# ECUTeen3_5_rev_A_20180308_1928.net
KiCad netlist of a schematic drawn in EAGLE
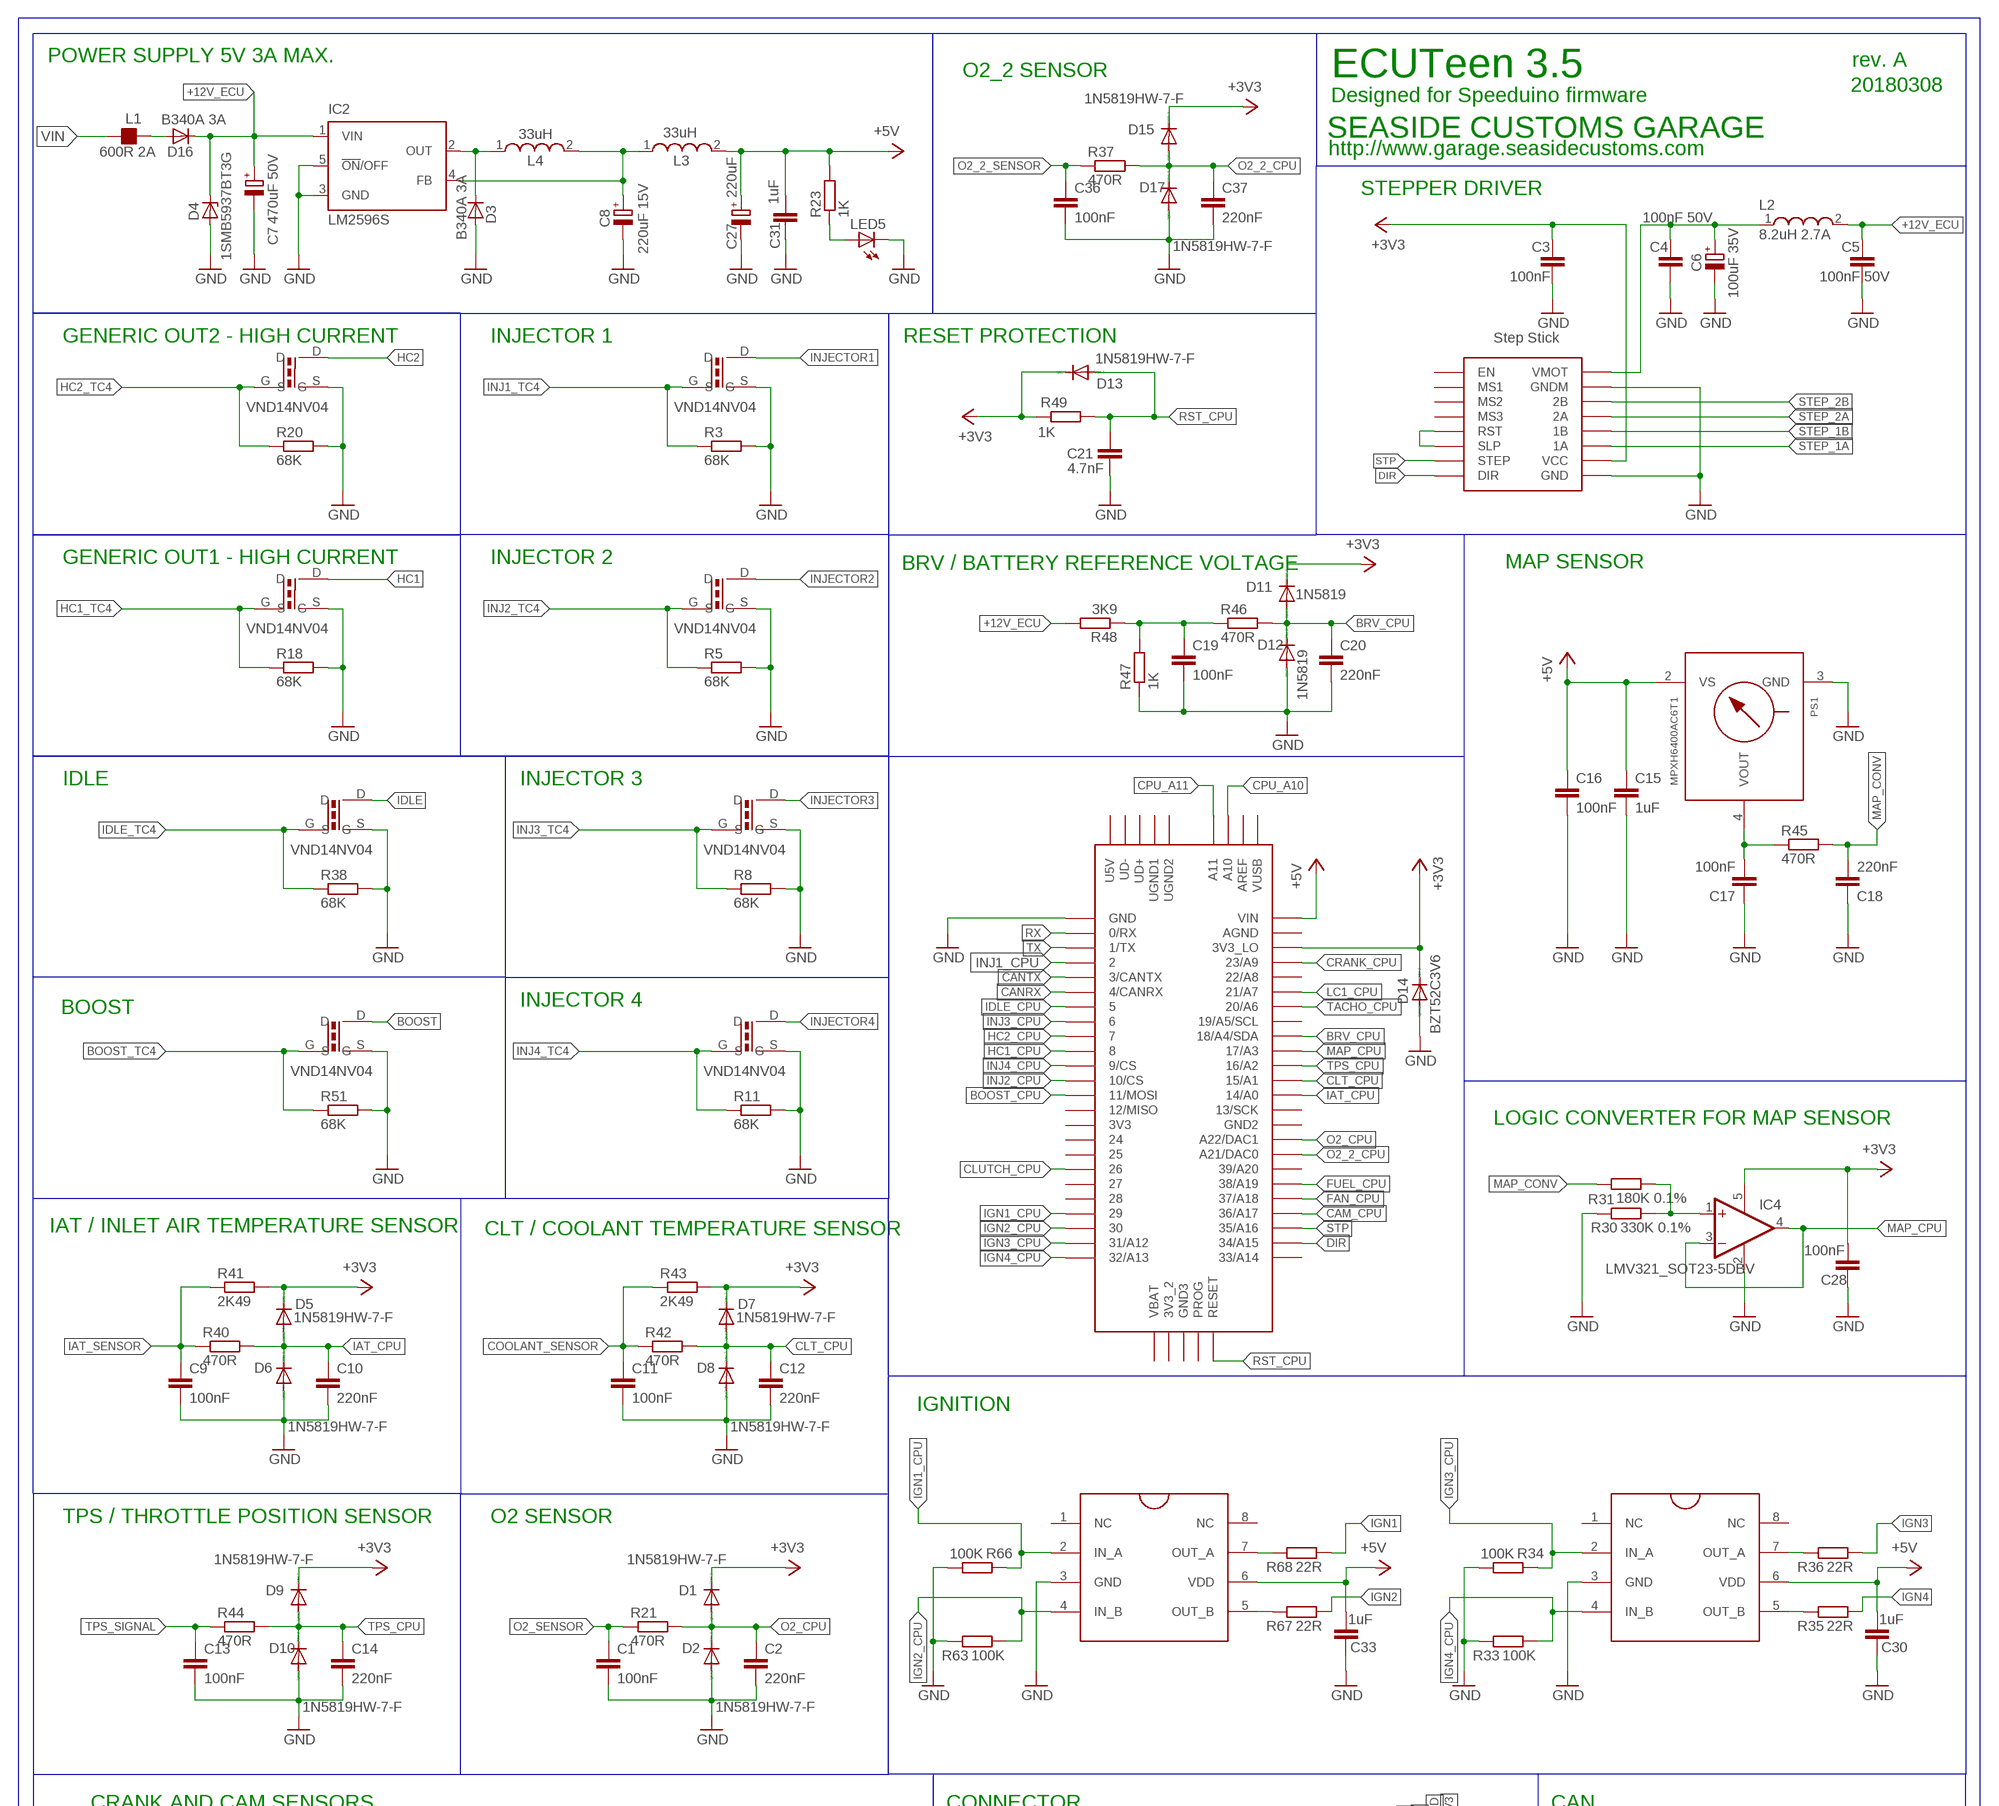
[diagram p0: schematic, sheet 1, part 1 of 2]
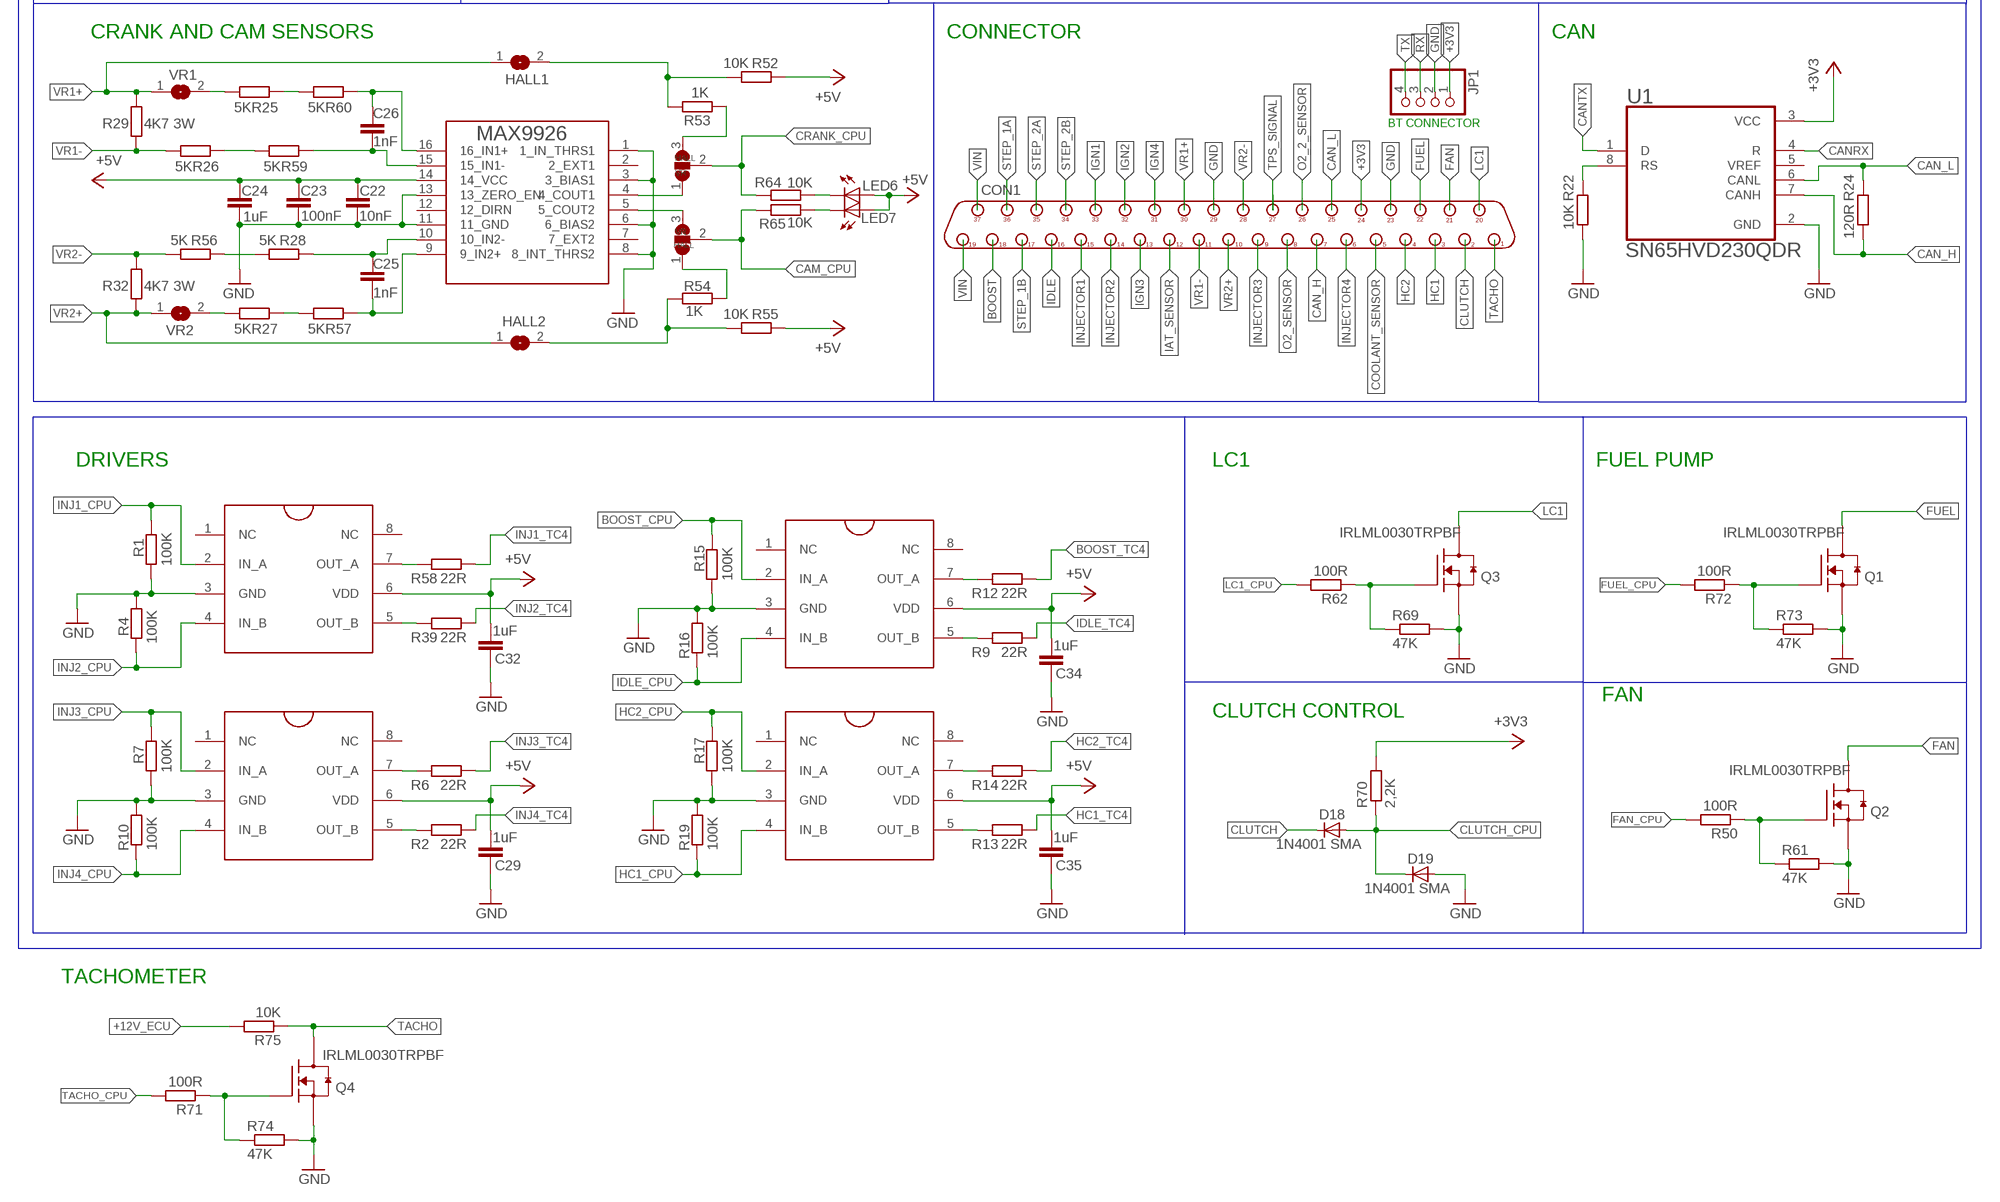
[diagram p1: schematic, sheet 1, part 2 of 2]

(export (version "E")
  (design (tool "Eeschema 10.0.6"))
  (components
    (comp (ref "C1")
      (value "100nF")
      (footprint "eagle-import:C0805")
      (libsource (lib "eagle-import") (part "C-EUC0805"))
    )
    (comp (ref "C2")
      (value "220nF")
      (footprint "eagle-import:C0805")
      (libsource (lib "eagle-import") (part "C-EUC0805"))
    )
    (comp (ref "C3")
      (value "100nF")
      (footprint "eagle-import:C0805")
      (libsource (lib "eagle-import") (part "C-EUC0805"))
    )
    (comp (ref "C4")
      (value "100nF 50V")
      (footprint "eagle-import:C0805")
      (libsource (lib "eagle-import") (part "C-EUC0805"))
    )
    (comp (ref "C5")
      (value "100nF 50V")
      (footprint "eagle-import:C0805")
      (libsource (lib "eagle-import") (part "C-EUC0805"))
    )
    (comp (ref "C6")
      (value "100uF 35V")
      (footprint "eagle-import:PANASONIC_D")
      (libsource (lib "eagle-import") (part "CPOL-EUD"))
    )
    (comp (ref "C7")
      (value "470uF 50V")
      (footprint "eagle-import:PANASONIC_D")
      (libsource (lib "eagle-import") (part "CPOL-EUD"))
    )
    (comp (ref "C8")
      (value "220uF 15V")
      (footprint "eagle-import:PANASONIC_D")
      (libsource (lib "eagle-import") (part "CPOL-EUD"))
    )
    (comp (ref "C9")
      (value "100nF")
      (footprint "eagle-import:C0805")
      (libsource (lib "eagle-import") (part "C-EUC0805"))
    )
    (comp (ref "C10")
      (value "220nF")
      (footprint "eagle-import:C0805")
      (libsource (lib "eagle-import") (part "C-EUC0805"))
    )
    (comp (ref "C11")
      (value "100nF")
      (footprint "eagle-import:C0805")
      (libsource (lib "eagle-import") (part "C-EUC0805"))
    )
    (comp (ref "C12")
      (value "220nF")
      (footprint "eagle-import:C0805")
      (libsource (lib "eagle-import") (part "C-EUC0805"))
    )
    (comp (ref "C13")
      (value "100nF")
      (footprint "eagle-import:C0805")
      (libsource (lib "eagle-import") (part "C-EUC0805"))
    )
    (comp (ref "C14")
      (value "220nF")
      (footprint "eagle-import:C0805")
      (libsource (lib "eagle-import") (part "C-EUC0805"))
    )
    (comp (ref "C15")
      (value "1uF")
      (footprint "eagle-import:C0805")
      (libsource (lib "eagle-import") (part "C-EUC0805"))
    )
    (comp (ref "C16")
      (value "100nF")
      (footprint "eagle-import:C0805")
      (libsource (lib "eagle-import") (part "C-EUC0805"))
    )
    (comp (ref "C17")
      (value "100nF")
      (footprint "eagle-import:C0805")
      (libsource (lib "eagle-import") (part "C-EUC0805"))
    )
    (comp (ref "C18")
      (value "220nF")
      (footprint "eagle-import:C0805")
      (libsource (lib "eagle-import") (part "C-EUC0805"))
    )
    (comp (ref "C19")
      (value "100nF")
      (footprint "eagle-import:C0805")
      (libsource (lib "eagle-import") (part "C-EUC0805"))
    )
    (comp (ref "C20")
      (value "220nF")
      (footprint "eagle-import:C0805")
      (libsource (lib "eagle-import") (part "C-EUC0805"))
    )
    (comp (ref "C21")
      (value "4.7nF")
      (footprint "eagle-import:C0805")
      (libsource (lib "eagle-import") (part "C-EUC0805"))
    )
    (comp (ref "C22")
      (value "10nF")
      (footprint "eagle-import:C0805")
      (libsource (lib "eagle-import") (part "C-EUC0805"))
    )
    (comp (ref "C23")
      (value "100nF")
      (footprint "eagle-import:C0805")
      (libsource (lib "eagle-import") (part "C-EUC0805"))
    )
    (comp (ref "C24")
      (value "1uF")
      (footprint "eagle-import:C0805")
      (libsource (lib "eagle-import") (part "C-EUC0805"))
    )
    (comp (ref "C25")
      (value "1nF")
      (footprint "eagle-import:C0805")
      (libsource (lib "eagle-import") (part "C-EUC0805"))
    )
    (comp (ref "C26")
      (value "1nF")
      (footprint "eagle-import:C0805")
      (libsource (lib "eagle-import") (part "C-EUC0805"))
    )
    (comp (ref "C27")
      (value "220uF")
      (footprint "eagle-import:PANASONIC_D")
      (libsource (lib "eagle-import") (part "CPOL-EUD"))
    )
    (comp (ref "C28")
      (value "100nF")
      (footprint "eagle-import:C0805")
      (libsource (lib "eagle-import") (part "C-EUC0805"))
    )
    (comp (ref "C29")
      (value "1uF")
      (footprint "eagle-import:C0805")
      (libsource (lib "eagle-import") (part "C-EUC0805"))
    )
    (comp (ref "C30")
      (value "1uF")
      (footprint "eagle-import:C0805")
      (libsource (lib "eagle-import") (part "C-EUC0805"))
    )
    (comp (ref "C31")
      (value "1uF")
      (footprint "eagle-import:C0805")
      (libsource (lib "eagle-import") (part "C-EUC0805"))
    )
    (comp (ref "C32")
      (value "1uF")
      (footprint "eagle-import:C0805")
      (libsource (lib "eagle-import") (part "C-EUC0805"))
    )
    (comp (ref "C33")
      (value "1uF")
      (footprint "eagle-import:C0805")
      (libsource (lib "eagle-import") (part "C-EUC0805"))
    )
    (comp (ref "C34")
      (value "1uF")
      (footprint "eagle-import:C0805")
      (libsource (lib "eagle-import") (part "C-EUC0805"))
    )
    (comp (ref "C35")
      (value "1uF")
      (footprint "eagle-import:C0805")
      (libsource (lib "eagle-import") (part "C-EUC0805"))
    )
    (comp (ref "C36")
      (value "100nF")
      (footprint "eagle-import:C0805")
      (libsource (lib "eagle-import") (part "C-EUC0805"))
    )
    (comp (ref "C37")
      (value "220nF")
      (footprint "eagle-import:C0805")
      (libsource (lib "eagle-import") (part "C-EUC0805"))
    )
    (comp (ref "CON1")
      (value "DB37M/90")
      (footprint "eagle-import:D-37M_90")
      (libsource (lib "eagle-import") (part "DB37M/90"))
    )
    (comp (ref "D1")
      (value "1N5819HW-7-F")
      (footprint "eagle-import:SOD123")
      (libsource (lib "eagle-import") (part "diode_DIODE-SOD123"))
    )
    (comp (ref "D2")
      (value "1N5819HW-7-F")
      (footprint "eagle-import:SOD123")
      (libsource (lib "eagle-import") (part "diode_DIODE-SOD123"))
    )
    (comp (ref "D3")
      (value "B340A 3A")
      (footprint "eagle-import:DO214AC")
      (fields (field (name "MF") "Fairchild") (field (name "MPN") "S1A"))
      (libsource (lib "eagle-import") (part "S1A"))
    )
    (comp (ref "D4")
      (value "1SMB5937BT3G")
      (footprint "eagle-import:SMB")
      (libsource (lib "eagle-import") (part "ZENER-DIODESMB"))
    )
    (comp (ref "D5")
      (value "1N5819HW-7-F")
      (footprint "eagle-import:SOD123")
      (libsource (lib "eagle-import") (part "diode_DIODE-SOD123"))
    )
    (comp (ref "D6")
      (value "1N5819HW-7-F")
      (footprint "eagle-import:SOD123")
      (libsource (lib "eagle-import") (part "diode_DIODE-SOD123"))
    )
    (comp (ref "D7")
      (value "1N5819HW-7-F")
      (footprint "eagle-import:SOD123")
      (libsource (lib "eagle-import") (part "diode_DIODE-SOD123"))
    )
    (comp (ref "D8")
      (value "1N5819HW-7-F")
      (footprint "eagle-import:SOD123")
      (libsource (lib "eagle-import") (part "diode_DIODE-SOD123"))
    )
    (comp (ref "D9")
      (value "1N5819HW-7-F")
      (footprint "eagle-import:SOD123")
      (libsource (lib "eagle-import") (part "diode_DIODE-SOD123"))
    )
    (comp (ref "D10")
      (value "1N5819HW-7-F")
      (footprint "eagle-import:SOD123")
      (libsource (lib "eagle-import") (part "diode_DIODE-SOD123"))
    )
    (comp (ref "D11")
      (value "1N5819")
      (footprint "eagle-import:SOD123")
      (libsource (lib "eagle-import") (part "diode_DIODE-SOD123"))
    )
    (comp (ref "D12")
      (value "1N5819")
      (footprint "eagle-import:SOD123")
      (libsource (lib "eagle-import") (part "diode_DIODE-SOD123"))
    )
    (comp (ref "D13")
      (value "1N5819HW-7-F")
      (footprint "eagle-import:SOD123")
      (libsource (lib "eagle-import") (part "diode_DIODE-SOD123"))
    )
    (comp (ref "D14")
      (value "BZT52C3V6")
      (footprint "eagle-import:SOD123")
      (libsource (lib "eagle-import") (part "DIODE-SOD123"))
    )
    (comp (ref "D15")
      (value "1N5819HW-7-F")
      (footprint "eagle-import:SOD123")
      (libsource (lib "eagle-import") (part "diode_DIODE-SOD123"))
    )
    (comp (ref "D16")
      (value "B340A 3A")
      (footprint "eagle-import:DO214AC")
      (fields (field (name "MF") "Fairchild") (field (name "MPN") "S1A"))
      (libsource (lib "eagle-import") (part "S1A"))
    )
    (comp (ref "D17")
      (value "1N5819HW-7-F")
      (footprint "eagle-import:SOD123")
      (libsource (lib "eagle-import") (part "diode_DIODE-SOD123"))
    )
    (comp (ref "D18")
      (value "1N4001 SMA")
      (footprint "eagle-import:DO214AC")
      (fields (field (name "MF") "Fairchild") (field (name "MPN") "S1A"))
      (libsource (lib "eagle-import") (part "S1A"))
    )
    (comp (ref "D19")
      (value "1N4001 SMA")
      (footprint "eagle-import:DO214AC")
      (fields (field (name "MF") "Fairchild") (field (name "MPN") "S1A"))
      (libsource (lib "eagle-import") (part "S1A"))
    )
    (comp (ref "IC2")
      (value "LM2596S")
      (footprint "eagle-import:TO263-5")
      (fields (field (name "MF") "NATIONAL SEMICONDUCTOR") (field (name "MPN") "LM2596S-ADJ/NOPB"))
      (libsource (lib "eagle-import") (part "LM2596S"))
    )
    (comp (ref "IC4")
      (value "LMV321_SOT23-5DBV")
      (footprint "eagle-import:SOT23-5")
      (libsource (lib "eagle-import") (part "LMV321_SOT23-5DBV"))
    )
    (comp (ref "JMP1")
      (value "SJ2W")
      (footprint "eagle-import:SJ_2")
      (libsource (lib "eagle-import") (part "SJ2W"))
    )
    (comp (ref "JMP2")
      (value "SJ2W")
      (footprint "eagle-import:SJ_2")
      (libsource (lib "eagle-import") (part "SJ2W"))
    )
    (comp (ref "JP1")
      (value "PINHD-1X4")
      (footprint "eagle-import:1X04")
      (libsource (lib "eagle-import") (part "PINHD-1X4"))
    )
    (comp (ref "L1")
      (value "600R 2A")
      (footprint "eagle-import:L1206")
      (libsource (lib "eagle-import") (part "FB_1206"))
    )
    (comp (ref "L2")
      (value "8.2uH 2.7A")
      (footprint "eagle-import:WE-PD_7332_7345_PLASTIC_BASE")
      (libsource (lib "eagle-import") (part "WE-PD_7332/7345_PLASTIC_BASE"))
    )
    (comp (ref "L3")
      (value "33uH")
      (footprint "eagle-import:WE-LHMI_7030_7050")
      (libsource (lib "eagle-import") (part "WE-LHMI_7030/7050"))
    )
    (comp (ref "L4")
      (value "33uH")
      (footprint "eagle-import:WE-LHMI_7030_7050")
      (libsource (lib "eagle-import") (part "WE-LHMI_7030/7050"))
    )
    (comp (ref "LED5")
      (value "LEDCHIP-LED0805")
      (footprint "eagle-import:CHIP-LED0805")
      (libsource (lib "eagle-import") (part "LEDCHIP-LED0805"))
    )
    (comp (ref "LED6")
      (value "LEDCHIP-LED0805")
      (footprint "eagle-import:CHIP-LED0805")
      (libsource (lib "eagle-import") (part "LEDCHIP-LED0805"))
    )
    (comp (ref "LED7")
      (value "LEDCHIP-LED0805")
      (footprint "eagle-import:CHIP-LED0805")
      (libsource (lib "eagle-import") (part "LEDCHIP-LED0805"))
    )
    (comp (ref "PS1")
      (value "MPXH6400AC6T1")
      (footprint "eagle-import:1317A")
      (libsource (lib "eagle-import") (part "MPXH6400AC6T1"))
    )
    (comp (ref "Q1")
      (value "IRLML0030TRPBF")
      (footprint "eagle-import:SOT95P280X135-3N")
      (libsource (lib "eagle-import") (part "MOSFET-NCH_SOT-23"))
    )
    (comp (ref "Q2")
      (value "IRLML0030TRPBF")
      (footprint "eagle-import:SOT95P280X135-3N")
      (libsource (lib "eagle-import") (part "MOSFET-NCH_SOT-23"))
    )
    (comp (ref "Q3")
      (value "IRLML0030TRPBF")
      (footprint "eagle-import:SOT95P280X135-3N")
      (libsource (lib "eagle-import") (part "MOSFET-NCH_SOT-23"))
    )
    (comp (ref "Q4")
      (value "IRLML0030TRPBF")
      (footprint "eagle-import:SOT95P280X135-3N")
      (libsource (lib "eagle-import") (part "MOSFET-NCH_SOT-23"))
    )
    (comp (ref "R1")
      (value "100K")
      (footprint "eagle-import:R0805")
      (libsource (lib "eagle-import") (part "R-EU_R0805"))
    )
    (comp (ref "R2")
      (value "22R")
      (footprint "eagle-import:R0805")
      (libsource (lib "eagle-import") (part "R-EU_R0805"))
    )
    (comp (ref "R3")
      (value "68K")
      (footprint "eagle-import:R0805")
      (libsource (lib "eagle-import") (part "R-EU_R0805"))
    )
    (comp (ref "R4")
      (value "100K")
      (footprint "eagle-import:R0805")
      (libsource (lib "eagle-import") (part "R-EU_R0805"))
    )
    (comp (ref "R5")
      (value "68K")
      (footprint "eagle-import:R0805")
      (libsource (lib "eagle-import") (part "R-EU_R0805"))
    )
    (comp (ref "R6")
      (value "22R")
      (footprint "eagle-import:R0805")
      (libsource (lib "eagle-import") (part "R-EU_R0805"))
    )
    (comp (ref "R7")
      (value "100K")
      (footprint "eagle-import:R0805")
      (libsource (lib "eagle-import") (part "R-EU_R0805"))
    )
    (comp (ref "R8")
      (value "68K")
      (footprint "eagle-import:R0805")
      (libsource (lib "eagle-import") (part "R-EU_R0805"))
    )
    (comp (ref "R9")
      (value "22R")
      (footprint "eagle-import:R0805")
      (libsource (lib "eagle-import") (part "R-EU_R0805"))
    )
    (comp (ref "R10")
      (value "100K")
      (footprint "eagle-import:R0805")
      (libsource (lib "eagle-import") (part "R-EU_R0805"))
    )
    (comp (ref "R11")
      (value "68K")
      (footprint "eagle-import:R0805")
      (libsource (lib "eagle-import") (part "R-EU_R0805"))
    )
    (comp (ref "R12")
      (value "22R")
      (footprint "eagle-import:R0805")
      (libsource (lib "eagle-import") (part "R-EU_R0805"))
    )
    (comp (ref "R13")
      (value "22R")
      (footprint "eagle-import:R0805")
      (libsource (lib "eagle-import") (part "R-EU_R0805"))
    )
    (comp (ref "R14")
      (value "22R")
      (footprint "eagle-import:R0805")
      (libsource (lib "eagle-import") (part "R-EU_R0805"))
    )
    (comp (ref "R15")
      (value "100K")
      (footprint "eagle-import:R0805")
      (libsource (lib "eagle-import") (part "R-EU_R0805"))
    )
    (comp (ref "R16")
      (value "100K")
      (footprint "eagle-import:R0805")
      (libsource (lib "eagle-import") (part "R-EU_R0805"))
    )
    (comp (ref "R17")
      (value "100K")
      (footprint "eagle-import:R0805")
      (libsource (lib "eagle-import") (part "R-EU_R0805"))
    )
    (comp (ref "R18")
      (value "68K")
      (footprint "eagle-import:R0805")
      (libsource (lib "eagle-import") (part "R-EU_R0805"))
    )
    (comp (ref "R19")
      (value "100K")
      (footprint "eagle-import:R0805")
      (libsource (lib "eagle-import") (part "R-EU_R0805"))
    )
    (comp (ref "R20")
      (value "68K")
      (footprint "eagle-import:R0805")
      (libsource (lib "eagle-import") (part "R-EU_R0805"))
    )
    (comp (ref "R21")
      (value "470R")
      (footprint "eagle-import:R0805")
      (libsource (lib "eagle-import") (part "R-EU_R0805"))
    )
    (comp (ref "R22")
      (value "10K")
      (footprint "eagle-import:R0805")
      (libsource (lib "eagle-import") (part "R-EU_R0805"))
    )
    (comp (ref "R23")
      (value "1K")
      (footprint "eagle-import:R0805")
      (libsource (lib "eagle-import") (part "R-EU_R0805"))
    )
    (comp (ref "R24")
      (value "120R")
      (footprint "eagle-import:R0805")
      (libsource (lib "eagle-import") (part "R-EU_R0805"))
    )
    (comp (ref "R25")
      (value "5K")
      (footprint "eagle-import:R0805")
      (libsource (lib "eagle-import") (part "R-EU_R0805"))
    )
    (comp (ref "R26")
      (value "5K")
      (footprint "eagle-import:R0805")
      (libsource (lib "eagle-import") (part "R-EU_R0805"))
    )
    (comp (ref "R27")
      (value "5K")
      (footprint "eagle-import:R0805")
      (libsource (lib "eagle-import") (part "R-EU_R0805"))
    )
    (comp (ref "R28")
      (value "5K")
      (footprint "eagle-import:R0805")
      (libsource (lib "eagle-import") (part "R-EU_R0805"))
    )
    (comp (ref "R29")
      (value "4K7 3W")
      (footprint "eagle-import:R2512")
      (libsource (lib "eagle-import") (part "R-EU_R2512"))
    )
    (comp (ref "R30")
      (value "330K 0.1%")
      (footprint "eagle-import:R0805")
      (libsource (lib "eagle-import") (part "R-EU_R0805"))
    )
    (comp (ref "R31")
      (value "180K 0.1%")
      (footprint "eagle-import:R0805")
      (libsource (lib "eagle-import") (part "R-EU_R0805"))
    )
    (comp (ref "R32")
      (value "4K7 3W")
      (footprint "eagle-import:R2512")
      (libsource (lib "eagle-import") (part "R-EU_R2512"))
    )
    (comp (ref "R33")
      (value "100K")
      (footprint "eagle-import:R0805")
      (libsource (lib "eagle-import") (part "R-EU_R0805"))
    )
    (comp (ref "R34")
      (value "100K")
      (footprint "eagle-import:R0805")
      (libsource (lib "eagle-import") (part "R-EU_R0805"))
    )
    (comp (ref "R35")
      (value "22R")
      (footprint "eagle-import:M1206")
      (libsource (lib "eagle-import") (part "R-EU_M1206"))
    )
    (comp (ref "R36")
      (value "22R")
      (footprint "eagle-import:M1206")
      (libsource (lib "eagle-import") (part "R-EU_M1206"))
    )
    (comp (ref "R37")
      (value "470R")
      (footprint "eagle-import:R0805")
      (libsource (lib "eagle-import") (part "R-EU_R0805"))
    )
    (comp (ref "R38")
      (value "68K")
      (footprint "eagle-import:R0805")
      (libsource (lib "eagle-import") (part "R-EU_R0805"))
    )
    (comp (ref "R39")
      (value "22R")
      (footprint "eagle-import:R0805")
      (libsource (lib "eagle-import") (part "R-EU_R0805"))
    )
    (comp (ref "R40")
      (value "470R")
      (footprint "eagle-import:R0805")
      (libsource (lib "eagle-import") (part "R-EU_R0805"))
    )
    (comp (ref "R41")
      (value "2K49")
      (footprint "eagle-import:R0805")
      (libsource (lib "eagle-import") (part "R-EU_R0805"))
    )
    (comp (ref "R42")
      (value "470R")
      (footprint "eagle-import:R0805")
      (libsource (lib "eagle-import") (part "R-EU_R0805"))
    )
    (comp (ref "R43")
      (value "2K49")
      (footprint "eagle-import:R0805")
      (libsource (lib "eagle-import") (part "R-EU_R0805"))
    )
    (comp (ref "R44")
      (value "470R")
      (footprint "eagle-import:R0805")
      (libsource (lib "eagle-import") (part "R-EU_R0805"))
    )
    (comp (ref "R45")
      (value "470R")
      (footprint "eagle-import:R0805")
      (libsource (lib "eagle-import") (part "R-EU_R0805"))
    )
    (comp (ref "R46")
      (value "470R")
      (footprint "eagle-import:R0805")
      (libsource (lib "eagle-import") (part "R-EU_R0805"))
    )
    (comp (ref "R47")
      (value "1K")
      (footprint "eagle-import:R0805")
      (libsource (lib "eagle-import") (part "R-EU_R0805"))
    )
    (comp (ref "R48")
      (value "3K9")
      (footprint "eagle-import:R0805")
      (libsource (lib "eagle-import") (part "R-EU_R0805"))
    )
    (comp (ref "R49")
      (value "1K")
      (footprint "eagle-import:R0805")
      (libsource (lib "eagle-import") (part "R-EU_R0805"))
    )
    (comp (ref "R50")
      (value "100R")
      (footprint "eagle-import:R0805")
      (libsource (lib "eagle-import") (part "R-EU_R0805"))
    )
    (comp (ref "R51")
      (value "68K")
      (footprint "eagle-import:R0805")
      (libsource (lib "eagle-import") (part "R-EU_R0805"))
    )
    (comp (ref "R52")
      (value "10K")
      (footprint "eagle-import:R0805")
      (libsource (lib "eagle-import") (part "R-EU_R0805"))
    )
    (comp (ref "R53")
      (value "1K")
      (footprint "eagle-import:R0805")
      (libsource (lib "eagle-import") (part "R-EU_R0805"))
    )
    (comp (ref "R54")
      (value "1K")
      (footprint "eagle-import:R0805")
      (libsource (lib "eagle-import") (part "R-EU_R0805"))
    )
    (comp (ref "R55")
      (value "10K")
      (footprint "eagle-import:R0805")
      (libsource (lib "eagle-import") (part "R-EU_R0805"))
    )
    (comp (ref "R56")
      (value "5K")
      (footprint "eagle-import:R0805")
      (libsource (lib "eagle-import") (part "R-EU_R0805"))
    )
    (comp (ref "R57")
      (value "5K")
      (footprint "eagle-import:R0805")
      (libsource (lib "eagle-import") (part "R-EU_R0805"))
    )
    (comp (ref "R58")
      (value "22R")
      (footprint "eagle-import:R0805")
      (libsource (lib "eagle-import") (part "R-EU_R0805"))
    )
    (comp (ref "R59")
      (value "5K")
      (footprint "eagle-import:R0805")
      (libsource (lib "eagle-import") (part "R-EU_R0805"))
    )
    (comp (ref "R60")
      (value "5K")
      (footprint "eagle-import:R0805")
      (libsource (lib "eagle-import") (part "R-EU_R0805"))
    )
    (comp (ref "R61")
      (value "47K")
      (footprint "eagle-import:R0805")
      (libsource (lib "eagle-import") (part "R-EU_R0805"))
    )
    (comp (ref "R62")
      (value "100R")
      (footprint "eagle-import:R0805")
      (libsource (lib "eagle-import") (part "R-EU_R0805"))
    )
    (comp (ref "R63")
      (value "100K")
      (footprint "eagle-import:R0805")
      (libsource (lib "eagle-import") (part "R-EU_R0805"))
    )
    (comp (ref "R64")
      (value "10K")
      (footprint "eagle-import:R0805")
      (libsource (lib "eagle-import") (part "R-EU_R0805"))
    )
    (comp (ref "R65")
      (value "10K")
      (footprint "eagle-import:R0805")
      (libsource (lib "eagle-import") (part "R-EU_R0805"))
    )
    (comp (ref "R66")
      (value "100K")
      (footprint "eagle-import:R0805")
      (libsource (lib "eagle-import") (part "R-EU_R0805"))
    )
    (comp (ref "R67")
      (value "22R")
      (footprint "eagle-import:M1206")
      (libsource (lib "eagle-import") (part "R-EU_M1206"))
    )
    (comp (ref "R68")
      (value "22R")
      (footprint "eagle-import:M1206")
      (libsource (lib "eagle-import") (part "R-EU_M1206"))
    )
    (comp (ref "R69")
      (value "47K")
      (footprint "eagle-import:R0805")
      (libsource (lib "eagle-import") (part "R-EU_R0805"))
    )
    (comp (ref "R70")
      (value "2,2K")
      (footprint "eagle-import:R0805")
      (libsource (lib "eagle-import") (part "R-EU_R0805"))
    )
    (comp (ref "R71")
      (value "100R")
      (footprint "eagle-import:R0805")
      (libsource (lib "eagle-import") (part "R-EU_R0805"))
    )
    (comp (ref "R72")
      (value "100R")
      (footprint "eagle-import:R0805")
      (libsource (lib "eagle-import") (part "R-EU_R0805"))
    )
    (comp (ref "R73")
      (value "47K")
      (footprint "eagle-import:R0805")
      (libsource (lib "eagle-import") (part "R-EU_R0805"))
    )
    (comp (ref "R74")
      (value "47K")
      (footprint "eagle-import:R0805")
      (libsource (lib "eagle-import") (part "R-EU_R0805"))
    )
    (comp (ref "R75")
      (value "10K")
      (footprint "eagle-import:R0805")
      (libsource (lib "eagle-import") (part "R-EU_R0805"))
    )
    (comp (ref "SJ3")
      (value "VR2")
      (footprint "eagle-import:SJ")
      (libsource (lib "eagle-import") (part "SJ"))
    )
    (comp (ref "SJ4")
      (value "VR1")
      (footprint "eagle-import:SJ")
      (libsource (lib "eagle-import") (part "SJ"))
    )
    (comp (ref "SJ5")
      (value "HALL2")
      (footprint "eagle-import:SJ")
      (libsource (lib "eagle-import") (part "SJ"))
    )
    (comp (ref "SJ6")
      (value "HALL1")
      (footprint "eagle-import:SJ")
      (libsource (lib "eagle-import") (part "SJ"))
    )
    (comp (ref "STEPSTICK-X")
      (value "STEP-STICK")
      (footprint "eagle-import:STEP-STICK")
      (libsource (lib "eagle-import") (part "STEP-STICK"))
    )
    (comp (ref "U$1")
      (value "TEENSY_3.5/3.6")
      (footprint "eagle-import:TEENSY_3.5_3.6")
      (libsource (lib "eagle-import") (part "TEENSY_3.5/3.6"))
    )
    (comp (ref "U$2")
      (value "DPAK_N-CHANNEL_MOSFET")
      (footprint "eagle-import:DPAK_N-CHANNEL_MOSFET")
      (libsource (lib "eagle-import") (part "DPAK_N-CHANNEL_MOSFET"))
    )
    (comp (ref "U$3")
      (value "DPAK_N-CHANNEL_MOSFET")
      (footprint "eagle-import:DPAK_N-CHANNEL_MOSFET")
      (libsource (lib "eagle-import") (part "DPAK_N-CHANNEL_MOSFET"))
    )
    (comp (ref "U$4")
      (value "DPAK_N-CHANNEL_MOSFET")
      (footprint "eagle-import:DPAK_N-CHANNEL_MOSFET")
      (libsource (lib "eagle-import") (part "DPAK_N-CHANNEL_MOSFET"))
    )
    (comp (ref "U$5")
      (value "DPAK_N-CHANNEL_MOSFET")
      (footprint "eagle-import:DPAK_N-CHANNEL_MOSFET")
      (libsource (lib "eagle-import") (part "DPAK_N-CHANNEL_MOSFET"))
    )
    (comp (ref "U$6")
      (value "DPAK_N-CHANNEL_MOSFET")
      (footprint "eagle-import:DPAK_N-CHANNEL_MOSFET")
      (libsource (lib "eagle-import") (part "DPAK_N-CHANNEL_MOSFET"))
    )
    (comp (ref "U$7")
      (value "TC427SO-8")
      (footprint "eagle-import:SO-8")
      (libsource (lib "eagle-import") (part "TC427SO-8"))
    )
    (comp (ref "U$8")
      (value "DPAK_N-CHANNEL_MOSFET")
      (footprint "eagle-import:DPAK_N-CHANNEL_MOSFET")
      (libsource (lib "eagle-import") (part "DPAK_N-CHANNEL_MOSFET"))
    )
    (comp (ref "U$9")
      (value "TC427SO-8")
      (footprint "eagle-import:SO-8")
      (libsource (lib "eagle-import") (part "TC427SO-8"))
    )
    (comp (ref "U$10")
      (value "MAX9926")
      (footprint "eagle-import:QSOP16")
      (libsource (lib "eagle-import") (part "MAX9926"))
    )
    (comp (ref "U$11")
      (value "TC427SO-8")
      (footprint "eagle-import:SO-8")
      (libsource (lib "eagle-import") (part "TC427SO-8"))
    )
    (comp (ref "U$12")
      (value "DPAK_N-CHANNEL_MOSFET")
      (footprint "eagle-import:DPAK_N-CHANNEL_MOSFET")
      (libsource (lib "eagle-import") (part "DPAK_N-CHANNEL_MOSFET"))
    )
    (comp (ref "U$13")
      (value "DPAK_N-CHANNEL_MOSFET")
      (footprint "eagle-import:DPAK_N-CHANNEL_MOSFET")
      (libsource (lib "eagle-import") (part "DPAK_N-CHANNEL_MOSFET"))
    )
    (comp (ref "U$14")
      (value "TC427SO-8")
      (footprint "eagle-import:SO-8")
      (libsource (lib "eagle-import") (part "TC427SO-8"))
    )
    (comp (ref "U$15")
      (value "TC427SO-8")
      (footprint "eagle-import:SO-8")
      (libsource (lib "eagle-import") (part "TC427SO-8"))
    )
    (comp (ref "U$16")
      (value "TC427SO-8")
      (footprint "eagle-import:SO-8")
      (libsource (lib "eagle-import") (part "TC427SO-8"))
    )
    (comp (ref "U1")
      (value "SN65HVD230QDR")
      (footprint "eagle-import:SOIC127P600X175-8N")
      (fields (field (name "MF") "Texas Instruments"))
      (libsource (lib "eagle-import") (part "SN65HVD230QDR"))
    )
  )
  (nets
    (net (code "2") (name "+3V3") (class "Default")
      (node (ref "C28") (pin "2") (pinfunction "2_2") (pintype "passive"))
      (node (ref "C3") (pin "1") (pinfunction "1_1") (pintype "passive"))
      (node (ref "CON1") (pin "24") (pinfunction "24_24") (pintype "passive"))
      (node (ref "D1") (pin "C") (pinfunction "C_C") (pintype "passive"))
      (node (ref "D11") (pin "C") (pinfunction "C_C") (pintype "passive"))
      (node (ref "D13") (pin "C") (pinfunction "C_C") (pintype "passive"))
      (node (ref "D14") (pin "C") (pinfunction "C_C") (pintype "passive"))
      (node (ref "D15") (pin "C") (pinfunction "C_C") (pintype "passive"))
      (node (ref "D5") (pin "C") (pinfunction "C_C") (pintype "passive"))
      (node (ref "D7") (pin "C") (pinfunction "C_C") (pintype "passive"))
      (node (ref "D9") (pin "C") (pinfunction "C_C") (pintype "passive"))
      (node (ref "IC4") (pin "5") (pinfunction "V+_5") (pintype "power_in"))
      (node (ref "JP1") (pin "1") (pinfunction "1_1") (pintype "passive"))
      (node (ref "R41") (pin "2") (pinfunction "2_2") (pintype "passive"))
      (node (ref "R43") (pin "2") (pinfunction "2_2") (pintype "passive"))
      (node (ref "R49") (pin "1") (pinfunction "1_1") (pintype "passive"))
      (node (ref "R70") (pin "2") (pinfunction "2_2") (pintype "passive"))
      (node (ref "STEPSTICK-X") (pin "VCC") (pinfunction "VCC_VCC") (pintype "bidirectional"))
      (node (ref "U$1") (pin "3V3_LO") (pinfunction "3V3_LO_3V3_LO") (pintype "bidirectional"))
      (node (ref "U1") (pin "3") (pinfunction "VCC_3") (pintype "power_in"))
    )
    (net (code "3") (name "+5V") (class "Default")
      (node (ref "C15") (pin "1") (pinfunction "1_1") (pintype "passive"))
      (node (ref "C16") (pin "1") (pinfunction "1_1") (pintype "passive"))
      (node (ref "C22") (pin "1") (pinfunction "1_1") (pintype "passive"))
      (node (ref "C23") (pin "1") (pinfunction "1_1") (pintype "passive"))
      (node (ref "C24") (pin "1") (pinfunction "1_1") (pintype "passive"))
      (node (ref "C27") (pin "+") (pinfunction "+_+") (pintype "passive"))
      (node (ref "C29") (pin "2") (pinfunction "2_2") (pintype "passive"))
      (node (ref "C30") (pin "2") (pinfunction "2_2") (pintype "passive"))
      (node (ref "C31") (pin "1") (pinfunction "1_1") (pintype "passive"))
      (node (ref "C32") (pin "2") (pinfunction "2_2") (pintype "passive"))
      (node (ref "C33") (pin "2") (pinfunction "2_2") (pintype "passive"))
      (node (ref "C34") (pin "2") (pinfunction "2_2") (pintype "passive"))
      (node (ref "C35") (pin "2") (pinfunction "2_2") (pintype "passive"))
      (node (ref "L3") (pin "2") (pinfunction "2_2") (pintype "passive"))
      (node (ref "LED6") (pin "A") (pinfunction "A_A") (pintype "passive"))
      (node (ref "LED7") (pin "A") (pinfunction "A_A") (pintype "passive"))
      (node (ref "PS1") (pin "2") (pinfunction "VS_2") (pintype "power_in"))
      (node (ref "R23") (pin "2") (pinfunction "2_2") (pintype "passive"))
      (node (ref "R52") (pin "1") (pinfunction "1_1") (pintype "passive"))
      (node (ref "R55") (pin "1") (pinfunction "1_1") (pintype "passive"))
      (node (ref "U$1") (pin "VIN") (pinfunction "VIN_VIN") (pintype "bidirectional"))
      (node (ref "U$10") (pin "14") (pinfunction "14_VCC_14") (pintype "bidirectional"))
      (node (ref "U$11") (pin "6") (pinfunction "VDD_6") (pintype "power_in"))
      (node (ref "U$14") (pin "6") (pinfunction "VDD_6") (pintype "power_in"))
      (node (ref "U$15") (pin "6") (pinfunction "VDD_6") (pintype "power_in"))
      (node (ref "U$16") (pin "6") (pinfunction "VDD_6") (pintype "power_in"))
      (node (ref "U$7") (pin "6") (pinfunction "VDD_6") (pintype "power_in"))
      (node (ref "U$9") (pin "6") (pinfunction "VDD_6") (pintype "power_in"))
    )
    (net (code "4") (name "+12V_ECU") (class "Default")
      (node (ref "C5") (pin "1") (pinfunction "1_1") (pintype "passive"))
      (node (ref "C7") (pin "+") (pinfunction "+_+") (pintype "passive"))
      (node (ref "D16") (pin "C") (pinfunction "C_C") (pintype "passive"))
      (node (ref "D4") (pin "C") (pinfunction "C_C") (pintype "passive"))
      (node (ref "IC2") (pin "1") (pinfunction "VIN_1") (pintype "input"))
      (node (ref "L2") (pin "2") (pinfunction "2_2") (pintype "passive"))
      (node (ref "R48") (pin "2") (pinfunction "2_2") (pintype "passive"))
      (node (ref "R75") (pin "2") (pinfunction "2_2") (pintype "passive"))
    )
    (net (code "6") (name "BOOST") (class "Default")
      (node (ref "CON1") (pin "18") (pinfunction "18_18") (pintype "passive"))
      (node (ref "U$13") (pin "D") (pinfunction "D_D") (pintype "bidirectional"))
    )
    (net (code "7") (name "BOOST_CPU") (class "Default")
      (node (ref "R15") (pin "2") (pinfunction "2_2") (pintype "passive"))
      (node (ref "U$1") (pin "11/MOSI") (pinfunction "11/MOSI_11/MOSI") (pintype "bidirectional"))
      (node (ref "U$15") (pin "2") (pinfunction "IN_A_2") (pintype "input"))
    )
    (net (code "8") (name "BOOST_TC4") (class "Default")
      (node (ref "R12") (pin "2") (pinfunction "2_2") (pintype "passive"))
      (node (ref "R51") (pin "1") (pinfunction "1_1") (pintype "passive"))
      (node (ref "U$13") (pin "G") (pinfunction "G_G") (pintype "bidirectional"))
    )
    (net (code "9") (name "BRV_CPU") (class "Default")
      (node (ref "C20") (pin "1") (pinfunction "1_1") (pintype "passive"))
      (node (ref "D11") (pin "A") (pinfunction "A_A") (pintype "passive"))
      (node (ref "D12") (pin "C") (pinfunction "C_C") (pintype "passive"))
      (node (ref "R46") (pin "2") (pinfunction "2_2") (pintype "passive"))
      (node (ref "U$1") (pin "18/A4/SDA") (pinfunction "18/A4/SDA_18/A4/SDA") (pintype "bidirectional"))
    )
    (net (code "10") (name "CAM_CPU") (class "Default")
      (node (ref "JMP2") (pin "2") (pinfunction "2_2") (pintype "passive"))
      (node (ref "R65") (pin "1") (pinfunction "1_1") (pintype "passive"))
      (node (ref "U$1") (pin "36/A17") (pinfunction "36/A17_36/A17") (pintype "bidirectional"))
    )
    (net (code "11") (name "CANRX") (class "Default")
      (node (ref "U$1") (pin "4/CANRX") (pinfunction "4/CANRX_4/CANRX") (pintype "bidirectional"))
      (node (ref "U1") (pin "4") (pinfunction "R_4") (pintype "output"))
    )
    (net (code "12") (name "CANTX") (class "Default")
      (node (ref "U$1") (pin "3/CANTX") (pinfunction "3/CANTX_3/CANTX") (pintype "bidirectional"))
      (node (ref "U1") (pin "1") (pinfunction "D_1") (pintype "input"))
    )
    (net (code "13") (name "CAN_H") (class "Default")
      (node (ref "CON1") (pin "7") (pinfunction "7_7") (pintype "passive"))
      (node (ref "R24") (pin "2") (pinfunction "2_2") (pintype "passive"))
      (node (ref "U1") (pin "7") (pinfunction "CANH_7") (pintype "output"))
    )
    (net (code "14") (name "CAN_L") (class "Default")
      (node (ref "CON1") (pin "25") (pinfunction "25_25") (pintype "passive"))
      (node (ref "R24") (pin "1") (pinfunction "1_1") (pintype "passive"))
      (node (ref "U1") (pin "6") (pinfunction "CANL_6") (pintype "output"))
    )
    (net (code "15") (name "CLT_CPU") (class "Default")
      (node (ref "C12") (pin "1") (pinfunction "1_1") (pintype "passive"))
      (node (ref "D7") (pin "A") (pinfunction "A_A") (pintype "passive"))
      (node (ref "D8") (pin "C") (pinfunction "C_C") (pintype "passive"))
      (node (ref "R42") (pin "2") (pinfunction "2_2") (pintype "passive"))
      (node (ref "U$1") (pin "15/A1") (pinfunction "15/A1_15/A1") (pintype "bidirectional"))
    )
    (net (code "16") (name "CLUTCH") (class "Default")
      (node (ref "CON1") (pin "2") (pinfunction "2_2") (pintype "passive"))
      (node (ref "D18") (pin "C") (pinfunction "C_C") (pintype "passive"))
    )
    (net (code "17") (name "CLUTCH_CPU") (class "Default")
      (node (ref "D18") (pin "A") (pinfunction "A_A") (pintype "passive"))
      (node (ref "D19") (pin "C") (pinfunction "C_C") (pintype "passive"))
      (node (ref "R70") (pin "1") (pinfunction "1_1") (pintype "passive"))
      (node (ref "U$1") (pin "26") (pinfunction "26_26") (pintype "bidirectional"))
    )
    (net (code "18") (name "COOLANT_SENSOR") (class "Default")
      (node (ref "C11") (pin "1") (pinfunction "1_1") (pintype "passive"))
      (node (ref "CON1") (pin "5") (pinfunction "5_5") (pintype "passive"))
      (node (ref "R42") (pin "1") (pinfunction "1_1") (pintype "passive"))
      (node (ref "R43") (pin "1") (pinfunction "1_1") (pintype "passive"))
    )
    (net (code "19") (name "CPU_A10") (class "Default")
      (node (ref "U$1") (pin "A10") (pinfunction "A10_A10") (pintype "bidirectional"))
    )
    (net (code "20") (name "CPU_A11") (class "Default")
      (node (ref "U$1") (pin "A11") (pinfunction "A11_A11") (pintype "bidirectional"))
    )
    (net (code "21") (name "CRANK_CPU") (class "Default")
      (node (ref "JMP1") (pin "2") (pinfunction "2_2") (pintype "passive"))
      (node (ref "R64") (pin "1") (pinfunction "1_1") (pintype "passive"))
      (node (ref "U$1") (pin "23/A9") (pinfunction "23/A9_23/A9") (pintype "bidirectional"))
    )
    (net (code "22") (name "DIR") (class "Default")
      (node (ref "STEPSTICK-X") (pin "DIR") (pinfunction "DIR_DIR") (pintype "bidirectional"))
      (node (ref "U$1") (pin "34/A15") (pinfunction "34/A15_34/A15") (pintype "bidirectional"))
    )
    (net (code "23") (name "FAN") (class "Default")
      (node (ref "CON1") (pin "21") (pinfunction "21_21") (pintype "passive"))
      (node (ref "Q2") (pin "3") (pinfunction "D_3") (pintype "passive"))
    )
    (net (code "24") (name "FAN_CPU") (class "Default")
      (node (ref "R50") (pin "2") (pinfunction "2_2") (pintype "passive"))
      (node (ref "U$1") (pin "37/A18") (pinfunction "37/A18_37/A18") (pintype "bidirectional"))
    )
    (net (code "25") (name "FUEL") (class "Default")
      (node (ref "CON1") (pin "22") (pinfunction "22_22") (pintype "passive"))
      (node (ref "Q1") (pin "3") (pinfunction "D_3") (pintype "passive"))
    )
    (net (code "26") (name "FUEL_CPU") (class "Default")
      (node (ref "R72") (pin "2") (pinfunction "2_2") (pintype "passive"))
      (node (ref "U$1") (pin "38/A19") (pinfunction "38/A19_38/A19") (pintype "bidirectional"))
    )
    (net (code "27") (name "GND") (class "Default")
      (node (ref "C1") (pin "2") (pinfunction "2_2") (pintype "passive"))
      (node (ref "C10") (pin "2") (pinfunction "2_2") (pintype "passive"))
      (node (ref "C11") (pin "2") (pinfunction "2_2") (pintype "passive"))
      (node (ref "C12") (pin "2") (pinfunction "2_2") (pintype "passive"))
      (node (ref "C13") (pin "2") (pinfunction "2_2") (pintype "passive"))
      (node (ref "C14") (pin "2") (pinfunction "2_2") (pintype "passive"))
      (node (ref "C15") (pin "2") (pinfunction "2_2") (pintype "passive"))
      (node (ref "C16") (pin "2") (pinfunction "2_2") (pintype "passive"))
      (node (ref "C17") (pin "1") (pinfunction "1_1") (pintype "passive"))
      (node (ref "C18") (pin "1") (pinfunction "1_1") (pintype "passive"))
      (node (ref "C19") (pin "2") (pinfunction "2_2") (pintype "passive"))
      (node (ref "C2") (pin "2") (pinfunction "2_2") (pintype "passive"))
      (node (ref "C20") (pin "2") (pinfunction "2_2") (pintype "passive"))
      (node (ref "C21") (pin "2") (pinfunction "2_2") (pintype "passive"))
      (node (ref "C22") (pin "2") (pinfunction "2_2") (pintype "passive"))
      (node (ref "C23") (pin "2") (pinfunction "2_2") (pintype "passive"))
      (node (ref "C24") (pin "2") (pinfunction "2_2") (pintype "passive"))
      (node (ref "C27") (pin "-") (pinfunction "-_-") (pintype "passive"))
      (node (ref "C28") (pin "1") (pinfunction "1_1") (pintype "passive"))
      (node (ref "C29") (pin "1") (pinfunction "1_1") (pintype "passive"))
      (node (ref "C3") (pin "2") (pinfunction "2_2") (pintype "passive"))
      (node (ref "C30") (pin "1") (pinfunction "1_1") (pintype "passive"))
      (node (ref "C31") (pin "2") (pinfunction "2_2") (pintype "passive"))
      (node (ref "C32") (pin "1") (pinfunction "1_1") (pintype "passive"))
      (node (ref "C33") (pin "1") (pinfunction "1_1") (pintype "passive"))
      (node (ref "C34") (pin "1") (pinfunction "1_1") (pintype "passive"))
      (node (ref "C35") (pin "1") (pinfunction "1_1") (pintype "passive"))
      (node (ref "C36") (pin "2") (pinfunction "2_2") (pintype "passive"))
      (node (ref "C37") (pin "2") (pinfunction "2_2") (pintype "passive"))
      (node (ref "C4") (pin "2") (pinfunction "2_2") (pintype "passive"))
      (node (ref "C5") (pin "2") (pinfunction "2_2") (pintype "passive"))
      (node (ref "C6") (pin "-") (pinfunction "-_-") (pintype "passive"))
      (node (ref "C7") (pin "-") (pinfunction "-_-") (pintype "passive"))
      (node (ref "C8") (pin "-") (pinfunction "-_-") (pintype "passive"))
      (node (ref "C9") (pin "2") (pinfunction "2_2") (pintype "passive"))
      (node (ref "CON1") (pin "23") (pinfunction "23_23") (pintype "passive"))
      (node (ref "CON1") (pin "29") (pinfunction "29_29") (pintype "passive"))
      (node (ref "D10") (pin "A") (pinfunction "A_A") (pintype "passive"))
      (node (ref "D12") (pin "A") (pinfunction "A_A") (pintype "passive"))
      (node (ref "D14") (pin "A") (pinfunction "A_A") (pintype "passive"))
      (node (ref "D17") (pin "A") (pinfunction "A_A") (pintype "passive"))
      (node (ref "D19") (pin "A") (pinfunction "A_A") (pintype "passive"))
      (node (ref "D2") (pin "A") (pinfunction "A_A") (pintype "passive"))
      (node (ref "D3") (pin "A") (pinfunction "A_A") (pintype "passive"))
      (node (ref "D4") (pin "A") (pinfunction "A_A") (pintype "passive"))
      (node (ref "D6") (pin "A") (pinfunction "A_A") (pintype "passive"))
      (node (ref "D8") (pin "A") (pinfunction "A_A") (pintype "passive"))
      (node (ref "IC2") (pin "3") (pinfunction "GND_3") (pintype "power_in"))
      (node (ref "IC2") (pin "5") (pinfunction "~{ON}/OFF_5") (pintype "input"))
      (node (ref "IC4") (pin "2") (pinfunction "V-_2") (pintype "power_in"))
      (node (ref "JP1") (pin "2") (pinfunction "2_2") (pintype "passive"))
      (node (ref "LED5") (pin "C") (pinfunction "C_C") (pintype "passive"))
      (node (ref "PS1") (pin "3") (pinfunction "GND_3") (pintype "power_in"))
      (node (ref "Q1") (pin "2") (pinfunction "S_2") (pintype "passive"))
      (node (ref "Q2") (pin "2") (pinfunction "S_2") (pintype "passive"))
      (node (ref "Q3") (pin "2") (pinfunction "S_2") (pintype "passive"))
      (node (ref "Q4") (pin "2") (pinfunction "S_2") (pintype "passive"))
      (node (ref "R1") (pin "1") (pinfunction "1_1") (pintype "passive"))
      (node (ref "R10") (pin "1") (pinfunction "1_1") (pintype "passive"))
      (node (ref "R11") (pin "2") (pinfunction "2_2") (pintype "passive"))
      (node (ref "R15") (pin "1") (pinfunction "1_1") (pintype "passive"))
      (node (ref "R16") (pin "1") (pinfunction "1_1") (pintype "passive"))
      (node (ref "R17") (pin "1") (pinfunction "1_1") (pintype "passive"))
      (node (ref "R18") (pin "2") (pinfunction "2_2") (pintype "passive"))
      (node (ref "R19") (pin "1") (pinfunction "1_1") (pintype "passive"))
      (node (ref "R20") (pin "2") (pinfunction "2_2") (pintype "passive"))
      (node (ref "R22") (pin "2") (pinfunction "2_2") (pintype "passive"))
      (node (ref "R3") (pin "2") (pinfunction "2_2") (pintype "passive"))
      (node (ref "R30") (pin "1") (pinfunction "1_1") (pintype "passive"))
      (node (ref "R33") (pin "1") (pinfunction "1_1") (pintype "passive"))
      (node (ref "R34") (pin "2") (pinfunction "2_2") (pintype "passive"))
      (node (ref "R38") (pin "2") (pinfunction "2_2") (pintype "passive"))
      (node (ref "R4") (pin "1") (pinfunction "1_1") (pintype "passive"))
      (node (ref "R47") (pin "1") (pinfunction "1_1") (pintype "passive"))
      (node (ref "R5") (pin "2") (pinfunction "2_2") (pintype "passive"))
      (node (ref "R51") (pin "2") (pinfunction "2_2") (pintype "passive"))
      (node (ref "R61") (pin "2") (pinfunction "2_2") (pintype "passive"))
      (node (ref "R63") (pin "1") (pinfunction "1_1") (pintype "passive"))
      (node (ref "R66") (pin "2") (pinfunction "2_2") (pintype "passive"))
      (node (ref "R69") (pin "2") (pinfunction "2_2") (pintype "passive"))
      (node (ref "R7") (pin "1") (pinfunction "1_1") (pintype "passive"))
      (node (ref "R73") (pin "2") (pinfunction "2_2") (pintype "passive"))
      (node (ref "R74") (pin "2") (pinfunction "2_2") (pintype "passive"))
      (node (ref "R8") (pin "2") (pinfunction "2_2") (pintype "passive"))
      (node (ref "STEPSTICK-X") (pin "GND") (pinfunction "GND_GND") (pintype "bidirectional"))
      (node (ref "STEPSTICK-X") (pin "GNDM") (pinfunction "GNDM_GNDM") (pintype "bidirectional"))
      (node (ref "U$1") (pin "GND") (pinfunction "GND_GND") (pintype "bidirectional"))
      (node (ref "U$10") (pin "1") (pinfunction "1_IN_THRS1_1") (pintype "bidirectional"))
      (node (ref "U$10") (pin "11") (pinfunction "11_GND_11") (pintype "bidirectional"))
      (node (ref "U$10") (pin "13") (pinfunction "13_ZERO_EN_13") (pintype "bidirectional"))
      (node (ref "U$10") (pin "3") (pinfunction "3_BIAS1_3") (pintype "bidirectional"))
      (node (ref "U$10") (pin "6") (pinfunction "6_BIAS2_6") (pintype "bidirectional"))
      (node (ref "U$10") (pin "8") (pinfunction "8_INT_THRS2_8") (pintype "bidirectional"))
      (node (ref "U$11") (pin "3") (pinfunction "GND_3") (pintype "power_in"))
      (node (ref "U$12") (pin "S") (pinfunction "S_S") (pintype "bidirectional"))
      (node (ref "U$13") (pin "S") (pinfunction "S_S") (pintype "bidirectional"))
      (node (ref "U$14") (pin "3") (pinfunction "GND_3") (pintype "power_in"))
      (node (ref "U$15") (pin "3") (pinfunction "GND_3") (pintype "power_in"))
      (node (ref "U$16") (pin "3") (pinfunction "GND_3") (pintype "power_in"))
      (node (ref "U$2") (pin "S") (pinfunction "S_S") (pintype "bidirectional"))
      (node (ref "U$3") (pin "S") (pinfunction "S_S") (pintype "bidirectional"))
      (node (ref "U$4") (pin "S") (pinfunction "S_S") (pintype "bidirectional"))
      (node (ref "U$5") (pin "S") (pinfunction "S_S") (pintype "bidirectional"))
      (node (ref "U$6") (pin "S") (pinfunction "S_S") (pintype "bidirectional"))
      (node (ref "U$7") (pin "3") (pinfunction "GND_3") (pintype "power_in"))
      (node (ref "U$8") (pin "S") (pinfunction "S_S") (pintype "bidirectional"))
      (node (ref "U$9") (pin "3") (pinfunction "GND_3") (pintype "power_in"))
      (node (ref "U1") (pin "2") (pinfunction "GND_2") (pintype "power_in"))
    )
    (net (code "28") (name "HC1") (class "Default")
      (node (ref "CON1") (pin "3") (pinfunction "3_3") (pintype "passive"))
      (node (ref "U$3") (pin "D") (pinfunction "D_D") (pintype "bidirectional"))
    )
    (net (code "29") (name "HC1_CPU") (class "Default")
      (node (ref "R19") (pin "2") (pinfunction "2_2") (pintype "passive"))
      (node (ref "U$1") (pin "8") (pinfunction "8_8") (pintype "bidirectional"))
      (node (ref "U$16") (pin "4") (pinfunction "IN_B_4") (pintype "input"))
    )
    (net (code "30") (name "HC1_TC4") (class "Default")
      (node (ref "R13") (pin "2") (pinfunction "2_2") (pintype "passive"))
      (node (ref "R18") (pin "1") (pinfunction "1_1") (pintype "passive"))
      (node (ref "U$3") (pin "G") (pinfunction "G_G") (pintype "bidirectional"))
    )
    (net (code "31") (name "HC2") (class "Default")
      (node (ref "CON1") (pin "4") (pinfunction "4_4") (pintype "passive"))
      (node (ref "U$2") (pin "D") (pinfunction "D_D") (pintype "bidirectional"))
    )
    (net (code "32") (name "HC2_CPU") (class "Default")
      (node (ref "R17") (pin "2") (pinfunction "2_2") (pintype "passive"))
      (node (ref "U$1") (pin "7") (pinfunction "7_7") (pintype "bidirectional"))
      (node (ref "U$16") (pin "2") (pinfunction "IN_A_2") (pintype "input"))
    )
    (net (code "33") (name "HC2_TC4") (class "Default")
      (node (ref "R14") (pin "2") (pinfunction "2_2") (pintype "passive"))
      (node (ref "R20") (pin "1") (pinfunction "1_1") (pintype "passive"))
      (node (ref "U$2") (pin "G") (pinfunction "G_G") (pintype "bidirectional"))
    )
    (net (code "34") (name "IAT_CPU") (class "Default")
      (node (ref "C10") (pin "1") (pinfunction "1_1") (pintype "passive"))
      (node (ref "D5") (pin "A") (pinfunction "A_A") (pintype "passive"))
      (node (ref "D6") (pin "C") (pinfunction "C_C") (pintype "passive"))
      (node (ref "R40") (pin "2") (pinfunction "2_2") (pintype "passive"))
      (node (ref "U$1") (pin "14/A0") (pinfunction "14/A0_14/A0") (pintype "bidirectional"))
    )
    (net (code "35") (name "IAT_SENSOR") (class "Default")
      (node (ref "C9") (pin "1") (pinfunction "1_1") (pintype "passive"))
      (node (ref "CON1") (pin "12") (pinfunction "12_12") (pintype "passive"))
      (node (ref "R40") (pin "1") (pinfunction "1_1") (pintype "passive"))
      (node (ref "R41") (pin "1") (pinfunction "1_1") (pintype "passive"))
    )
    (net (code "36") (name "IDLE") (class "Default")
      (node (ref "CON1") (pin "16") (pinfunction "16_16") (pintype "passive"))
      (node (ref "U$5") (pin "D") (pinfunction "D_D") (pintype "bidirectional"))
    )
    (net (code "37") (name "IDLE_CPU") (class "Default")
      (node (ref "R16") (pin "2") (pinfunction "2_2") (pintype "passive"))
      (node (ref "U$1") (pin "5") (pinfunction "5_5") (pintype "bidirectional"))
      (node (ref "U$15") (pin "4") (pinfunction "IN_B_4") (pintype "input"))
    )
    (net (code "38") (name "IDLE_TC4") (class "Default")
      (node (ref "R38") (pin "1") (pinfunction "1_1") (pintype "passive"))
      (node (ref "R9") (pin "2") (pinfunction "2_2") (pintype "passive"))
      (node (ref "U$5") (pin "G") (pinfunction "G_G") (pintype "bidirectional"))
    )
    (net (code "39") (name "IGN1") (class "Default")
      (node (ref "CON1") (pin "33") (pinfunction "33_33") (pintype "passive"))
      (node (ref "R68") (pin "2") (pinfunction "2_2") (pintype "passive"))
    )
    (net (code "40") (name "IGN1_CPU") (class "Default")
      (node (ref "R66") (pin "1") (pinfunction "1_1") (pintype "passive"))
      (node (ref "U$1") (pin "29") (pinfunction "29_29") (pintype "bidirectional"))
      (node (ref "U$9") (pin "2") (pinfunction "IN_A_2") (pintype "input"))
    )
    (net (code "41") (name "IGN2") (class "Default")
      (node (ref "CON1") (pin "32") (pinfunction "32_32") (pintype "passive"))
      (node (ref "R67") (pin "2") (pinfunction "2_2") (pintype "passive"))
    )
    (net (code "42") (name "IGN2_CPU") (class "Default")
      (node (ref "R63") (pin "2") (pinfunction "2_2") (pintype "passive"))
      (node (ref "U$1") (pin "30") (pinfunction "30_30") (pintype "bidirectional"))
      (node (ref "U$9") (pin "4") (pinfunction "IN_B_4") (pintype "input"))
    )
    (net (code "43") (name "IGN3") (class "Default")
      (node (ref "CON1") (pin "13") (pinfunction "13_13") (pintype "passive"))
      (node (ref "R36") (pin "2") (pinfunction "2_2") (pintype "passive"))
    )
    (net (code "44") (name "IGN3_CPU") (class "Default")
      (node (ref "R34") (pin "1") (pinfunction "1_1") (pintype "passive"))
      (node (ref "U$1") (pin "31/A12") (pinfunction "31/A12_31/A12") (pintype "bidirectional"))
      (node (ref "U$11") (pin "2") (pinfunction "IN_A_2") (pintype "input"))
    )
    (net (code "45") (name "IGN4") (class "Default")
      (node (ref "CON1") (pin "31") (pinfunction "31_31") (pintype "passive"))
      (node (ref "R35") (pin "2") (pinfunction "2_2") (pintype "passive"))
    )
    (net (code "46") (name "IGN4_CPU") (class "Default")
      (node (ref "R33") (pin "2") (pinfunction "2_2") (pintype "passive"))
      (node (ref "U$1") (pin "32/A13") (pinfunction "32/A13_32/A13") (pintype "bidirectional"))
      (node (ref "U$11") (pin "4") (pinfunction "IN_B_4") (pintype "input"))
    )
    (net (code "47") (name "INJ1_CPU") (class "Default")
      (node (ref "R1") (pin "2") (pinfunction "2_2") (pintype "passive"))
      (node (ref "U$1") (pin "2") (pinfunction "2_2") (pintype "bidirectional"))
      (node (ref "U$14") (pin "2") (pinfunction "IN_A_2") (pintype "input"))
    )
    (net (code "48") (name "INJ1_TC4") (class "Default")
      (node (ref "R3") (pin "1") (pinfunction "1_1") (pintype "passive"))
      (node (ref "R58") (pin "2") (pinfunction "2_2") (pintype "passive"))
      (node (ref "U$12") (pin "G") (pinfunction "G_G") (pintype "bidirectional"))
    )
    (net (code "49") (name "INJ2_CPU") (class "Default")
      (node (ref "R4") (pin "2") (pinfunction "2_2") (pintype "passive"))
      (node (ref "U$1") (pin "10/CS") (pinfunction "10/CS_10/CS") (pintype "bidirectional"))
      (node (ref "U$14") (pin "4") (pinfunction "IN_B_4") (pintype "input"))
    )
    (net (code "50") (name "INJ2_TC4") (class "Default")
      (node (ref "R39") (pin "2") (pinfunction "2_2") (pintype "passive"))
      (node (ref "R5") (pin "1") (pinfunction "1_1") (pintype "passive"))
      (node (ref "U$4") (pin "G") (pinfunction "G_G") (pintype "bidirectional"))
    )
    (net (code "51") (name "INJ3_CPU") (class "Default")
      (node (ref "R7") (pin "2") (pinfunction "2_2") (pintype "passive"))
      (node (ref "U$1") (pin "6") (pinfunction "6_6") (pintype "bidirectional"))
      (node (ref "U$7") (pin "2") (pinfunction "IN_A_2") (pintype "input"))
    )
    (net (code "52") (name "INJ3_TC4") (class "Default")
      (node (ref "R6") (pin "2") (pinfunction "2_2") (pintype "passive"))
      (node (ref "R8") (pin "1") (pinfunction "1_1") (pintype "passive"))
      (node (ref "U$6") (pin "G") (pinfunction "G_G") (pintype "bidirectional"))
    )
    (net (code "53") (name "INJ4_CPU") (class "Default")
      (node (ref "R10") (pin "2") (pinfunction "2_2") (pintype "passive"))
      (node (ref "U$1") (pin "9/CS") (pinfunction "9/CS_9/CS") (pintype "bidirectional"))
      (node (ref "U$7") (pin "4") (pinfunction "IN_B_4") (pintype "input"))
    )
    (net (code "54") (name "INJ4_TC4") (class "Default")
      (node (ref "R11") (pin "1") (pinfunction "1_1") (pintype "passive"))
      (node (ref "R2") (pin "2") (pinfunction "2_2") (pintype "passive"))
      (node (ref "U$8") (pin "G") (pinfunction "G_G") (pintype "bidirectional"))
    )
    (net (code "55") (name "INJECTOR1") (class "Default")
      (node (ref "CON1") (pin "15") (pinfunction "15_15") (pintype "passive"))
      (node (ref "U$12") (pin "D") (pinfunction "D_D") (pintype "bidirectional"))
    )
    (net (code "56") (name "INJECTOR2") (class "Default")
      (node (ref "CON1") (pin "14") (pinfunction "14_14") (pintype "passive"))
      (node (ref "U$4") (pin "D") (pinfunction "D_D") (pintype "bidirectional"))
    )
    (net (code "57") (name "INJECTOR3") (class "Default")
      (node (ref "CON1") (pin "9") (pinfunction "9_9") (pintype "passive"))
      (node (ref "U$6") (pin "D") (pinfunction "D_D") (pintype "bidirectional"))
    )
    (net (code "58") (name "INJECTOR4") (class "Default")
      (node (ref "CON1") (pin "6") (pinfunction "6_6") (pintype "passive"))
      (node (ref "U$8") (pin "D") (pinfunction "D_D") (pintype "bidirectional"))
    )
    (net (code "59") (name "LC1") (class "Default")
      (node (ref "CON1") (pin "20") (pinfunction "20_20") (pintype "passive"))
      (node (ref "Q3") (pin "3") (pinfunction "D_3") (pintype "passive"))
    )
    (net (code "60") (name "LC1_CPU") (class "Default")
      (node (ref "R62") (pin "2") (pinfunction "2_2") (pintype "passive"))
      (node (ref "U$1") (pin "21/A7") (pinfunction "21/A7_21/A7") (pintype "bidirectional"))
    )
    (net (code "61") (name "MAP_CONV") (class "Default")
      (node (ref "C18") (pin "2") (pinfunction "2_2") (pintype "passive"))
      (node (ref "R31") (pin "2") (pinfunction "2_2") (pintype "passive"))
      (node (ref "R45") (pin "2") (pinfunction "2_2") (pintype "passive"))
    )
    (net (code "62") (name "MAP_CPU") (class "Default")
      (node (ref "IC4") (pin "3") (pinfunction "-IN_3") (pintype "input"))
      (node (ref "IC4") (pin "4") (pinfunction "OUT_4") (pintype "output"))
      (node (ref "U$1") (pin "17/A3") (pinfunction "17/A3_17/A3") (pintype "bidirectional"))
    )
    (net (code "63") (name "Net-(C4-Pad1)") (class "Default")
      (node (ref "C4") (pin "1") (pinfunction "1_1") (pintype "passive"))
      (node (ref "C6") (pin "+") (pinfunction "+_+") (pintype "passive"))
      (node (ref "L2") (pin "1") (pinfunction "1_1") (pintype "passive"))
      (node (ref "STEPSTICK-X") (pin "VMOT") (pinfunction "VMOT_VMOT") (pintype "bidirectional"))
    )
    (net (code "64") (name "Net-(C19-Pad1)") (class "Default")
      (node (ref "C19") (pin "1") (pinfunction "1_1") (pintype "passive"))
      (node (ref "R46") (pin "1") (pinfunction "1_1") (pintype "passive"))
      (node (ref "R47") (pin "2") (pinfunction "2_2") (pintype "passive"))
      (node (ref "R48") (pin "1") (pinfunction "1_1") (pintype "passive"))
    )
    (net (code "65") (name "Net-(D16-PadA)") (class "Default")
      (node (ref "D16") (pin "A") (pinfunction "A_A") (pintype "passive"))
      (node (ref "L1") (pin "1") (pinfunction "1_1") (pintype "passive"))
    )
    (net (code "66") (name "Net-(IC2-FB)") (class "Default")
      (node (ref "C8") (pin "+") (pinfunction "+_+") (pintype "passive"))
      (node (ref "IC2") (pin "4") (pinfunction "FB_4") (pintype "input"))
      (node (ref "L3") (pin "1") (pinfunction "1_1") (pintype "passive"))
      (node (ref "L4") (pin "2") (pinfunction "2_2") (pintype "passive"))
    )
    (net (code "67") (name "Net-(IC2-OUT)") (class "Default")
      (node (ref "D3") (pin "C") (pinfunction "C_C") (pintype "passive"))
      (node (ref "IC2") (pin "2") (pinfunction "OUT_2") (pintype "output"))
      (node (ref "L4") (pin "1") (pinfunction "1_1") (pintype "passive"))
    )
    (net (code "68") (name "Net-(IC4-+IN)") (class "Default")
      (node (ref "IC4") (pin "1") (pinfunction "+IN_1") (pintype "input"))
      (node (ref "R30") (pin "2") (pinfunction "2_2") (pintype "passive"))
      (node (ref "R31") (pin "1") (pinfunction "1_1") (pintype "passive"))
    )
    (net (code "69") (name "Net-(JMP1-Pad3)") (class "Default")
      (node (ref "JMP1") (pin "3") (pinfunction "3_3") (pintype "passive"))
      (node (ref "R53") (pin "2") (pinfunction "2_2") (pintype "passive"))
    )
    (net (code "70") (name "Net-(JMP2-Pad1)") (class "Default")
      (node (ref "JMP2") (pin "1") (pinfunction "1_1") (pintype "passive"))
      (node (ref "R54") (pin "1") (pinfunction "1_1") (pintype "passive"))
    )
    (net (code "71") (name "Net-(LED5-PadA)") (class "Default")
      (node (ref "LED5") (pin "A") (pinfunction "A_A") (pintype "passive"))
      (node (ref "R23") (pin "1") (pinfunction "1_1") (pintype "passive"))
    )
    (net (code "72") (name "Net-(LED6-PadC)") (class "Default")
      (node (ref "LED6") (pin "C") (pinfunction "C_C") (pintype "passive"))
      (node (ref "R64") (pin "2") (pinfunction "2_2") (pintype "passive"))
    )
    (net (code "73") (name "Net-(LED7-PadC)") (class "Default")
      (node (ref "LED7") (pin "C") (pinfunction "C_C") (pintype "passive"))
      (node (ref "R65") (pin "2") (pinfunction "2_2") (pintype "passive"))
    )
    (net (code "74") (name "Net-(PS1-VOUT)") (class "Default")
      (node (ref "C17") (pin "2") (pinfunction "2_2") (pintype "passive"))
      (node (ref "PS1") (pin "4") (pinfunction "VOUT_4") (pintype "output"))
      (node (ref "R45") (pin "1") (pinfunction "1_1") (pintype "passive"))
    )
    (net (code "75") (name "Net-(Q1-G)") (class "Default")
      (node (ref "Q1") (pin "1") (pinfunction "G_1") (pintype "passive"))
      (node (ref "R72") (pin "1") (pinfunction "1_1") (pintype "passive"))
      (node (ref "R73") (pin "1") (pinfunction "1_1") (pintype "passive"))
    )
    (net (code "76") (name "Net-(Q2-G)") (class "Default")
      (node (ref "Q2") (pin "1") (pinfunction "G_1") (pintype "passive"))
      (node (ref "R50") (pin "1") (pinfunction "1_1") (pintype "passive"))
      (node (ref "R61") (pin "1") (pinfunction "1_1") (pintype "passive"))
    )
    (net (code "77") (name "Net-(Q3-G)") (class "Default")
      (node (ref "Q3") (pin "1") (pinfunction "G_1") (pintype "passive"))
      (node (ref "R62") (pin "1") (pinfunction "1_1") (pintype "passive"))
      (node (ref "R69") (pin "1") (pinfunction "1_1") (pintype "passive"))
    )
    (net (code "78") (name "Net-(Q4-G)") (class "Default")
      (node (ref "Q4") (pin "1") (pinfunction "G_1") (pintype "passive"))
      (node (ref "R71") (pin "1") (pinfunction "1_1") (pintype "passive"))
      (node (ref "R74") (pin "1") (pinfunction "1_1") (pintype "passive"))
    )
    (net (code "79") (name "Net-(R25-Pad1)") (class "Default")
      (node (ref "R25") (pin "1") (pinfunction "1_1") (pintype "passive"))
      (node (ref "R60") (pin "2") (pinfunction "2_2") (pintype "passive"))
    )
    (net (code "80") (name "Net-(R25-Pad2)") (class "Default")
      (node (ref "R25") (pin "2") (pinfunction "2_2") (pintype "passive"))
      (node (ref "SJ4") (pin "2") (pinfunction "2_2") (pintype "passive"))
    )
    (net (code "81") (name "Net-(R26-Pad1)") (class "Default")
      (node (ref "R26") (pin "1") (pinfunction "1_1") (pintype "passive"))
      (node (ref "R59") (pin "2") (pinfunction "2_2") (pintype "passive"))
    )
    (net (code "82") (name "Net-(R27-Pad1)") (class "Default")
      (node (ref "R27") (pin "1") (pinfunction "1_1") (pintype "passive"))
      (node (ref "R57") (pin "2") (pinfunction "2_2") (pintype "passive"))
    )
    (net (code "83") (name "Net-(R27-Pad2)") (class "Default")
      (node (ref "R27") (pin "2") (pinfunction "2_2") (pintype "passive"))
      (node (ref "SJ3") (pin "2") (pinfunction "2_2") (pintype "passive"))
    )
    (net (code "84") (name "Net-(R28-Pad2)") (class "Default")
      (node (ref "R28") (pin "2") (pinfunction "2_2") (pintype "passive"))
      (node (ref "R56") (pin "1") (pinfunction "1_1") (pintype "passive"))
    )
    (net (code "85") (name "Net-(R52-Pad2)") (class "Default")
      (node (ref "R52") (pin "2") (pinfunction "2_2") (pintype "passive"))
      (node (ref "R53") (pin "1") (pinfunction "1_1") (pintype "passive"))
      (node (ref "SJ6") (pin "2") (pinfunction "2_2") (pintype "passive"))
    )
    (net (code "86") (name "Net-(R54-Pad2)") (class "Default")
      (node (ref "R54") (pin "2") (pinfunction "2_2") (pintype "passive"))
      (node (ref "R55") (pin "2") (pinfunction "2_2") (pintype "passive"))
      (node (ref "SJ5") (pin "2") (pinfunction "2_2") (pintype "passive"))
    )
    (net (code "87") (name "Net-(STEPSTICK-X-PadRST)") (class "Default")
      (node (ref "STEPSTICK-X") (pin "RST") (pinfunction "RST_RST") (pintype "bidirectional"))
      (node (ref "STEPSTICK-X") (pin "SLP") (pinfunction "SLP_SLP") (pintype "bidirectional"))
    )
    (net (code "88") (name "Net-(U$7-OUT_A)") (class "Default")
      (node (ref "R6") (pin "1") (pinfunction "1_1") (pintype "passive"))
      (node (ref "U$7") (pin "7") (pinfunction "OUT_A_7") (pintype "output"))
    )
    (net (code "89") (name "Net-(U$7-OUT_B)") (class "Default")
      (node (ref "R2") (pin "1") (pinfunction "1_1") (pintype "passive"))
      (node (ref "U$7") (pin "5") (pinfunction "OUT_B_5") (pintype "output"))
    )
    (net (code "90") (name "Net-(U$9-OUT_A)") (class "Default")
      (node (ref "R68") (pin "1") (pinfunction "1_1") (pintype "passive"))
      (node (ref "U$9") (pin "7") (pinfunction "OUT_A_7") (pintype "output"))
    )
    (net (code "91") (name "Net-(U$9-OUT_B)") (class "Default")
      (node (ref "R67") (pin "1") (pinfunction "1_1") (pintype "passive"))
      (node (ref "U$9") (pin "5") (pinfunction "OUT_B_5") (pintype "output"))
    )
    (net (code "92") (name "Net-(U$10-4_COUT1)") (class "Default")
      (node (ref "JMP1") (pin "1") (pinfunction "1_1") (pintype "passive"))
      (node (ref "U$10") (pin "4") (pinfunction "4_COUT1_4") (pintype "bidirectional"))
    )
    (net (code "93") (name "Net-(U$10-5_COUT2)") (class "Default")
      (node (ref "JMP2") (pin "3") (pinfunction "3_3") (pintype "passive"))
      (node (ref "U$10") (pin "5") (pinfunction "5_COUT2_5") (pintype "bidirectional"))
    )
    (net (code "94") (name "Net-(U$10-9_IN2+)") (class "Default")
      (node (ref "C25") (pin "2") (pinfunction "2_2") (pintype "passive"))
      (node (ref "R57") (pin "1") (pinfunction "1_1") (pintype "passive"))
      (node (ref "U$10") (pin "9") (pinfunction "9_IN2+_9") (pintype "bidirectional"))
    )
    (net (code "95") (name "Net-(U$10-10_IN2-)") (class "Default")
      (node (ref "C25") (pin "1") (pinfunction "1_1") (pintype "passive"))
      (node (ref "R28") (pin "1") (pinfunction "1_1") (pintype "passive"))
      (node (ref "U$10") (pin "10") (pinfunction "10_IN2-_10") (pintype "bidirectional"))
    )
    (net (code "96") (name "Net-(U$10-15_IN1-)") (class "Default")
      (node (ref "C26") (pin "2") (pinfunction "2_2") (pintype "passive"))
      (node (ref "R59") (pin "1") (pinfunction "1_1") (pintype "passive"))
      (node (ref "U$10") (pin "15") (pinfunction "15_IN1-_15") (pintype "bidirectional"))
    )
    (net (code "97") (name "Net-(U$10-16_IN1+)") (class "Default")
      (node (ref "C26") (pin "1") (pinfunction "1_1") (pintype "passive"))
      (node (ref "R60") (pin "1") (pinfunction "1_1") (pintype "passive"))
      (node (ref "U$10") (pin "16") (pinfunction "16_IN1+_16") (pintype "bidirectional"))
    )
    (net (code "98") (name "Net-(U$11-OUT_A)") (class "Default")
      (node (ref "R36") (pin "1") (pinfunction "1_1") (pintype "passive"))
      (node (ref "U$11") (pin "7") (pinfunction "OUT_A_7") (pintype "output"))
    )
    (net (code "99") (name "Net-(U$11-OUT_B)") (class "Default")
      (node (ref "R35") (pin "1") (pinfunction "1_1") (pintype "passive"))
      (node (ref "U$11") (pin "5") (pinfunction "OUT_B_5") (pintype "output"))
    )
    (net (code "100") (name "Net-(U$14-OUT_A)") (class "Default")
      (node (ref "R58") (pin "1") (pinfunction "1_1") (pintype "passive"))
      (node (ref "U$14") (pin "7") (pinfunction "OUT_A_7") (pintype "output"))
    )
    (net (code "101") (name "Net-(U$14-OUT_B)") (class "Default")
      (node (ref "R39") (pin "1") (pinfunction "1_1") (pintype "passive"))
      (node (ref "U$14") (pin "5") (pinfunction "OUT_B_5") (pintype "output"))
    )
    (net (code "102") (name "Net-(U$15-OUT_A)") (class "Default")
      (node (ref "R12") (pin "1") (pinfunction "1_1") (pintype "passive"))
      (node (ref "U$15") (pin "7") (pinfunction "OUT_A_7") (pintype "output"))
    )
    (net (code "103") (name "Net-(U$15-OUT_B)") (class "Default")
      (node (ref "R9") (pin "1") (pinfunction "1_1") (pintype "passive"))
      (node (ref "U$15") (pin "5") (pinfunction "OUT_B_5") (pintype "output"))
    )
    (net (code "104") (name "Net-(U$16-OUT_A)") (class "Default")
      (node (ref "R14") (pin "1") (pinfunction "1_1") (pintype "passive"))
      (node (ref "U$16") (pin "7") (pinfunction "OUT_A_7") (pintype "output"))
    )
    (net (code "105") (name "Net-(U$16-OUT_B)") (class "Default")
      (node (ref "R13") (pin "1") (pinfunction "1_1") (pintype "passive"))
      (node (ref "U$16") (pin "5") (pinfunction "OUT_B_5") (pintype "output"))
    )
    (net (code "106") (name "Net-(U1-RS)") (class "Default")
      (node (ref "R22") (pin "1") (pinfunction "1_1") (pintype "passive"))
      (node (ref "U1") (pin "8") (pinfunction "RS_8") (pintype "input"))
    )
    (net (code "107") (name "O2_2_CPU") (class "Default")
      (node (ref "C37") (pin "1") (pinfunction "1_1") (pintype "passive"))
      (node (ref "D15") (pin "A") (pinfunction "A_A") (pintype "passive"))
      (node (ref "D17") (pin "C") (pinfunction "C_C") (pintype "passive"))
      (node (ref "R37") (pin "2") (pinfunction "2_2") (pintype "passive"))
      (node (ref "U$1") (pin "21/DAC0") (pinfunction "A21/DAC0_21/DAC0") (pintype "bidirectional"))
    )
    (net (code "108") (name "O2_2_SENSOR") (class "Default")
      (node (ref "C36") (pin "1") (pinfunction "1_1") (pintype "passive"))
      (node (ref "CON1") (pin "26") (pinfunction "26_26") (pintype "passive"))
      (node (ref "R37") (pin "1") (pinfunction "1_1") (pintype "passive"))
    )
    (net (code "109") (name "O2_CPU") (class "Default")
      (node (ref "C2") (pin "1") (pinfunction "1_1") (pintype "passive"))
      (node (ref "D1") (pin "A") (pinfunction "A_A") (pintype "passive"))
      (node (ref "D2") (pin "C") (pinfunction "C_C") (pintype "passive"))
      (node (ref "R21") (pin "2") (pinfunction "2_2") (pintype "passive"))
      (node (ref "U$1") (pin "A22/DAC1") (pinfunction "A22/DAC1_A22/DAC1") (pintype "bidirectional"))
    )
    (net (code "110") (name "O2_SENSOR") (class "Default")
      (node (ref "C1") (pin "1") (pinfunction "1_1") (pintype "passive"))
      (node (ref "CON1") (pin "8") (pinfunction "8_8") (pintype "passive"))
      (node (ref "R21") (pin "1") (pinfunction "1_1") (pintype "passive"))
    )
    (net (code "111") (name "RST_CPU") (class "Default")
      (node (ref "C21") (pin "1") (pinfunction "1_1") (pintype "passive"))
      (node (ref "D13") (pin "A") (pinfunction "A_A") (pintype "passive"))
      (node (ref "R49") (pin "2") (pinfunction "2_2") (pintype "passive"))
      (node (ref "U$1") (pin "RESET") (pinfunction "RESET_RESET") (pintype "bidirectional"))
    )
    (net (code "112") (name "RX") (class "Default")
      (node (ref "JP1") (pin "3") (pinfunction "3_3") (pintype "passive"))
      (node (ref "U$1") (pin "0/RX") (pinfunction "0/RX_0/RX") (pintype "bidirectional"))
    )
    (net (code "113") (name "STEP_1A") (class "Default")
      (node (ref "CON1") (pin "36") (pinfunction "36_36") (pintype "passive"))
      (node (ref "STEPSTICK-X") (pin "1A") (pinfunction "1A_1A") (pintype "bidirectional"))
    )
    (net (code "114") (name "STEP_1B") (class "Default")
      (node (ref "CON1") (pin "17") (pinfunction "17_17") (pintype "passive"))
      (node (ref "STEPSTICK-X") (pin "1B") (pinfunction "1B_1B") (pintype "bidirectional"))
    )
    (net (code "115") (name "STEP_2A") (class "Default")
      (node (ref "CON1") (pin "35") (pinfunction "35_35") (pintype "passive"))
      (node (ref "STEPSTICK-X") (pin "2A") (pinfunction "2A_2A") (pintype "bidirectional"))
    )
    (net (code "116") (name "STEP_2B") (class "Default")
      (node (ref "CON1") (pin "34") (pinfunction "34_34") (pintype "passive"))
      (node (ref "STEPSTICK-X") (pin "2B") (pinfunction "2B_2B") (pintype "bidirectional"))
    )
    (net (code "117") (name "STP") (class "Default")
      (node (ref "STEPSTICK-X") (pin "SPT") (pinfunction "STEP_SPT") (pintype "bidirectional"))
      (node (ref "U$1") (pin "35/A16") (pinfunction "35/A16_35/A16") (pintype "bidirectional"))
    )
    (net (code "118") (name "TACHO") (class "Default")
      (node (ref "CON1") (pin "1") (pinfunction "1_1") (pintype "passive"))
      (node (ref "Q4") (pin "3") (pinfunction "D_3") (pintype "passive"))
      (node (ref "R75") (pin "1") (pinfunction "1_1") (pintype "passive"))
    )
    (net (code "119") (name "TACHO_CPU") (class "Default")
      (node (ref "R71") (pin "2") (pinfunction "2_2") (pintype "passive"))
      (node (ref "U$1") (pin "20/A6") (pinfunction "20/A6_20/A6") (pintype "bidirectional"))
    )
    (net (code "120") (name "TPS_CPU") (class "Default")
      (node (ref "C14") (pin "1") (pinfunction "1_1") (pintype "passive"))
      (node (ref "D10") (pin "C") (pinfunction "C_C") (pintype "passive"))
      (node (ref "D9") (pin "A") (pinfunction "A_A") (pintype "passive"))
      (node (ref "R44") (pin "2") (pinfunction "2_2") (pintype "passive"))
      (node (ref "U$1") (pin "16/A2") (pinfunction "16/A2_16/A2") (pintype "bidirectional"))
    )
    (net (code "121") (name "TPS_SIGNAL") (class "Default")
      (node (ref "C13") (pin "1") (pinfunction "1_1") (pintype "passive"))
      (node (ref "CON1") (pin "27") (pinfunction "27_27") (pintype "passive"))
      (node (ref "R44") (pin "1") (pinfunction "1_1") (pintype "passive"))
    )
    (net (code "122") (name "TX") (class "Default")
      (node (ref "JP1") (pin "4") (pinfunction "4_4") (pintype "passive"))
      (node (ref "U$1") (pin "1/TX") (pinfunction "1/TX_1/TX") (pintype "bidirectional"))
    )
    (net (code "123") (name "VIN") (class "Default")
      (node (ref "CON1") (pin "19") (pinfunction "19_19") (pintype "passive"))
      (node (ref "CON1") (pin "37") (pinfunction "37_37") (pintype "passive"))
      (node (ref "L1") (pin "2") (pinfunction "2_2") (pintype "passive"))
    )
    (net (code "124") (name "VR1+") (class "Default")
      (node (ref "CON1") (pin "30") (pinfunction "30_30") (pintype "passive"))
      (node (ref "R29") (pin "1") (pinfunction "1_1") (pintype "passive"))
      (node (ref "SJ4") (pin "1") (pinfunction "1_1") (pintype "passive"))
      (node (ref "SJ6") (pin "1") (pinfunction "1_1") (pintype "passive"))
    )
    (net (code "125") (name "VR1-") (class "Default")
      (node (ref "CON1") (pin "11") (pinfunction "11_11") (pintype "passive"))
      (node (ref "R26") (pin "2") (pinfunction "2_2") (pintype "passive"))
      (node (ref "R29") (pin "2") (pinfunction "2_2") (pintype "passive"))
    )
    (net (code "126") (name "VR2+") (class "Default")
      (node (ref "CON1") (pin "10") (pinfunction "10_10") (pintype "passive"))
      (node (ref "R32") (pin "2") (pinfunction "2_2") (pintype "passive"))
      (node (ref "SJ3") (pin "1") (pinfunction "1_1") (pintype "passive"))
      (node (ref "SJ5") (pin "1") (pinfunction "1_1") (pintype "passive"))
    )
    (net (code "127") (name "VR2-") (class "Default")
      (node (ref "CON1") (pin "28") (pinfunction "28_28") (pintype "passive"))
      (node (ref "R32") (pin "1") (pinfunction "1_1") (pintype "passive"))
      (node (ref "R56") (pin "2") (pinfunction "2_2") (pintype "passive"))
    )
    (net (code "128") (name "unconnected-(PS1-NC-Pad1)") (class "Default")
      (node (ref "PS1") (pin "1") (pinfunction "NC_1") (pintype "no_connect"))
    )
    (net (code "129") (name "unconnected-(PS1-NC-Pad5)") (class "Default")
      (node (ref "PS1") (pin "5") (pinfunction "NC_5") (pintype "no_connect"))
    )
    (net (code "130") (name "unconnected-(PS1-NC-Pad6)") (class "Default")
      (node (ref "PS1") (pin "6") (pinfunction "NC_6") (pintype "no_connect"))
    )
    (net (code "131") (name "unconnected-(STEPSTICK-X-PadEN)") (class "Default")
      (node (ref "STEPSTICK-X") (pin "EN") (pinfunction "EN_EN") (pintype "bidirectional"))
    )
    (net (code "132") (name "unconnected-(STEPSTICK-X-PadMS1)") (class "Default")
      (node (ref "STEPSTICK-X") (pin "MS1") (pinfunction "MS1_MS1") (pintype "bidirectional"))
    )
    (net (code "133") (name "unconnected-(STEPSTICK-X-PadMS2)") (class "Default")
      (node (ref "STEPSTICK-X") (pin "MS2") (pinfunction "MS2_MS2") (pintype "bidirectional"))
    )
    (net (code "134") (name "unconnected-(STEPSTICK-X-PadMS3)") (class "Default")
      (node (ref "STEPSTICK-X") (pin "MS3") (pinfunction "MS3_MS3") (pintype "bidirectional"))
    )
    (net (code "135") (name "unconnected-(U$1-Pad3V3)") (class "Default")
      (node (ref "U$1") (pin "3V3") (pinfunction "3V3_3V3") (pintype "bidirectional"))
    )
    (net (code "136") (name "unconnected-(U$1-Pad3V3_2)") (class "Default")
      (node (ref "U$1") (pin "3V3_2") (pinfunction "3V3_2_3V3_2") (pintype "bidirectional"))
    )
    (net (code "137") (name "unconnected-(U$1-Pad12{slash}MISO)") (class "Default")
      (node (ref "U$1") (pin "12/MISO") (pinfunction "12/MISO_12/MISO") (pintype "bidirectional"))
    )
    (net (code "138") (name "unconnected-(U$1-Pad13{slash}SCK)") (class "Default")
      (node (ref "U$1") (pin "13/SCK") (pinfunction "13/SCK_13/SCK") (pintype "bidirectional"))
    )
    (net (code "139") (name "unconnected-(U$1-Pad19{slash}A5{slash}SCL)") (class "Default")
      (node (ref "U$1") (pin "19/A5/SCL") (pinfunction "19/A5/SCL_19/A5/SCL") (pintype "bidirectional"))
    )
    (net (code "140") (name "unconnected-(U$1-Pad22{slash}A8)") (class "Default")
      (node (ref "U$1") (pin "22/A8") (pinfunction "22/A8_22/A8") (pintype "bidirectional"))
    )
    (net (code "141") (name "unconnected-(U$1-Pad24)") (class "Default")
      (node (ref "U$1") (pin "24") (pinfunction "24_24") (pintype "bidirectional"))
    )
    (net (code "142") (name "unconnected-(U$1-Pad25)") (class "Default")
      (node (ref "U$1") (pin "25") (pinfunction "25_25") (pintype "bidirectional"))
    )
    (net (code "143") (name "unconnected-(U$1-Pad27)") (class "Default")
      (node (ref "U$1") (pin "27") (pinfunction "27_27") (pintype "bidirectional"))
    )
    (net (code "144") (name "unconnected-(U$1-Pad28)") (class "Default")
      (node (ref "U$1") (pin "28") (pinfunction "28_28") (pintype "bidirectional"))
    )
    (net (code "145") (name "unconnected-(U$1-Pad33{slash}A14)") (class "Default")
      (node (ref "U$1") (pin "33/A14") (pinfunction "33/A14_33/A14") (pintype "bidirectional"))
    )
    (net (code "146") (name "unconnected-(U$1-Pad39{slash}A20)") (class "Default")
      (node (ref "U$1") (pin "39/A20") (pinfunction "39/A20_39/A20") (pintype "bidirectional"))
    )
    (net (code "147") (name "unconnected-(U$1-PadAGND)") (class "Default")
      (node (ref "U$1") (pin "AGND") (pinfunction "AGND_AGND") (pintype "bidirectional"))
    )
    (net (code "148") (name "unconnected-(U$1-PadAREF)") (class "Default")
      (node (ref "U$1") (pin "AREF") (pinfunction "AREF_AREF") (pintype "bidirectional"))
    )
    (net (code "149") (name "unconnected-(U$1-PadGND2)") (class "Default")
      (node (ref "U$1") (pin "GND2") (pinfunction "GND2_GND2") (pintype "bidirectional"))
    )
    (net (code "150") (name "unconnected-(U$1-PadGND3)") (class "Default")
      (node (ref "U$1") (pin "GND3") (pinfunction "GND3_GND3") (pintype "bidirectional"))
    )
    (net (code "151") (name "unconnected-(U$1-PadPROG)") (class "Default")
      (node (ref "U$1") (pin "PROG") (pinfunction "PROG_PROG") (pintype "bidirectional"))
    )
    (net (code "152") (name "unconnected-(U$1-PadU5V)") (class "Default")
      (node (ref "U$1") (pin "U5V") (pinfunction "U5V_U5V") (pintype "bidirectional"))
    )
    (net (code "153") (name "unconnected-(U$1-PadUD+)") (class "Default")
      (node (ref "U$1") (pin "UD+") (pinfunction "UD+_UD+") (pintype "bidirectional"))
    )
    (net (code "154") (name "unconnected-(U$1-PadUD-)") (class "Default")
      (node (ref "U$1") (pin "UD-") (pinfunction "UD-_UD-") (pintype "bidirectional"))
    )
    (net (code "155") (name "unconnected-(U$1-PadUGND1)") (class "Default")
      (node (ref "U$1") (pin "UGND1") (pinfunction "UGND1_UGND1") (pintype "bidirectional"))
    )
    (net (code "156") (name "unconnected-(U$1-PadUGND2)") (class "Default")
      (node (ref "U$1") (pin "UGND2") (pinfunction "UGND2_UGND2") (pintype "bidirectional"))
    )
    (net (code "157") (name "unconnected-(U$1-PadVBAT)") (class "Default")
      (node (ref "U$1") (pin "VBAT") (pinfunction "VBAT_VBAT") (pintype "bidirectional"))
    )
    (net (code "158") (name "unconnected-(U$1-PadVUSB)") (class "Default")
      (node (ref "U$1") (pin "VUSB") (pinfunction "VUSB_VUSB") (pintype "bidirectional"))
    )
    (net (code "159") (name "unconnected-(U$7-NC-Pad1)") (class "Default")
      (node (ref "U$7") (pin "1") (pinfunction "NC_1") (pintype "no_connect"))
    )
    (net (code "160") (name "unconnected-(U$7-NC-Pad8)") (class "Default")
      (node (ref "U$7") (pin "8") (pinfunction "NC_8") (pintype "no_connect"))
    )
    (net (code "161") (name "unconnected-(U$9-NC-Pad1)") (class "Default")
      (node (ref "U$9") (pin "1") (pinfunction "NC_1") (pintype "no_connect"))
    )
    (net (code "162") (name "unconnected-(U$9-NC-Pad8)") (class "Default")
      (node (ref "U$9") (pin "8") (pinfunction "NC_8") (pintype "no_connect"))
    )
    (net (code "163") (name "unconnected-(U$10-2_EXT1-Pad2)") (class "Default")
      (node (ref "U$10") (pin "2") (pinfunction "2_EXT1_2") (pintype "bidirectional"))
    )
    (net (code "164") (name "unconnected-(U$10-7_EXT2-Pad7)") (class "Default")
      (node (ref "U$10") (pin "7") (pinfunction "7_EXT2_7") (pintype "bidirectional"))
    )
    (net (code "165") (name "unconnected-(U$10-12_DIRN-Pad12)") (class "Default")
      (node (ref "U$10") (pin "12") (pinfunction "12_DIRN_12") (pintype "bidirectional"))
    )
    (net (code "166") (name "unconnected-(U$11-NC-Pad1)") (class "Default")
      (node (ref "U$11") (pin "1") (pinfunction "NC_1") (pintype "no_connect"))
    )
    (net (code "167") (name "unconnected-(U$11-NC-Pad8)") (class "Default")
      (node (ref "U$11") (pin "8") (pinfunction "NC_8") (pintype "no_connect"))
    )
    (net (code "168") (name "unconnected-(U$14-NC-Pad1)") (class "Default")
      (node (ref "U$14") (pin "1") (pinfunction "NC_1") (pintype "no_connect"))
    )
    (net (code "169") (name "unconnected-(U$14-NC-Pad8)") (class "Default")
      (node (ref "U$14") (pin "8") (pinfunction "NC_8") (pintype "no_connect"))
    )
    (net (code "170") (name "unconnected-(U$15-NC-Pad1)") (class "Default")
      (node (ref "U$15") (pin "1") (pinfunction "NC_1") (pintype "no_connect"))
    )
    (net (code "171") (name "unconnected-(U$15-NC-Pad8)") (class "Default")
      (node (ref "U$15") (pin "8") (pinfunction "NC_8") (pintype "no_connect"))
    )
    (net (code "172") (name "unconnected-(U$16-NC-Pad1)") (class "Default")
      (node (ref "U$16") (pin "1") (pinfunction "NC_1") (pintype "no_connect"))
    )
    (net (code "173") (name "unconnected-(U$16-NC-Pad8)") (class "Default")
      (node (ref "U$16") (pin "8") (pinfunction "NC_8") (pintype "no_connect"))
    )
    (net (code "174") (name "unconnected-(U1-VREF-Pad5)") (class "Default")
      (node (ref "U1") (pin "5") (pinfunction "VREF_5") (pintype "output"))
    )
  )
)
